# PT08ttl3.net
KiCad netlist of a schematic drawn in EAGLE
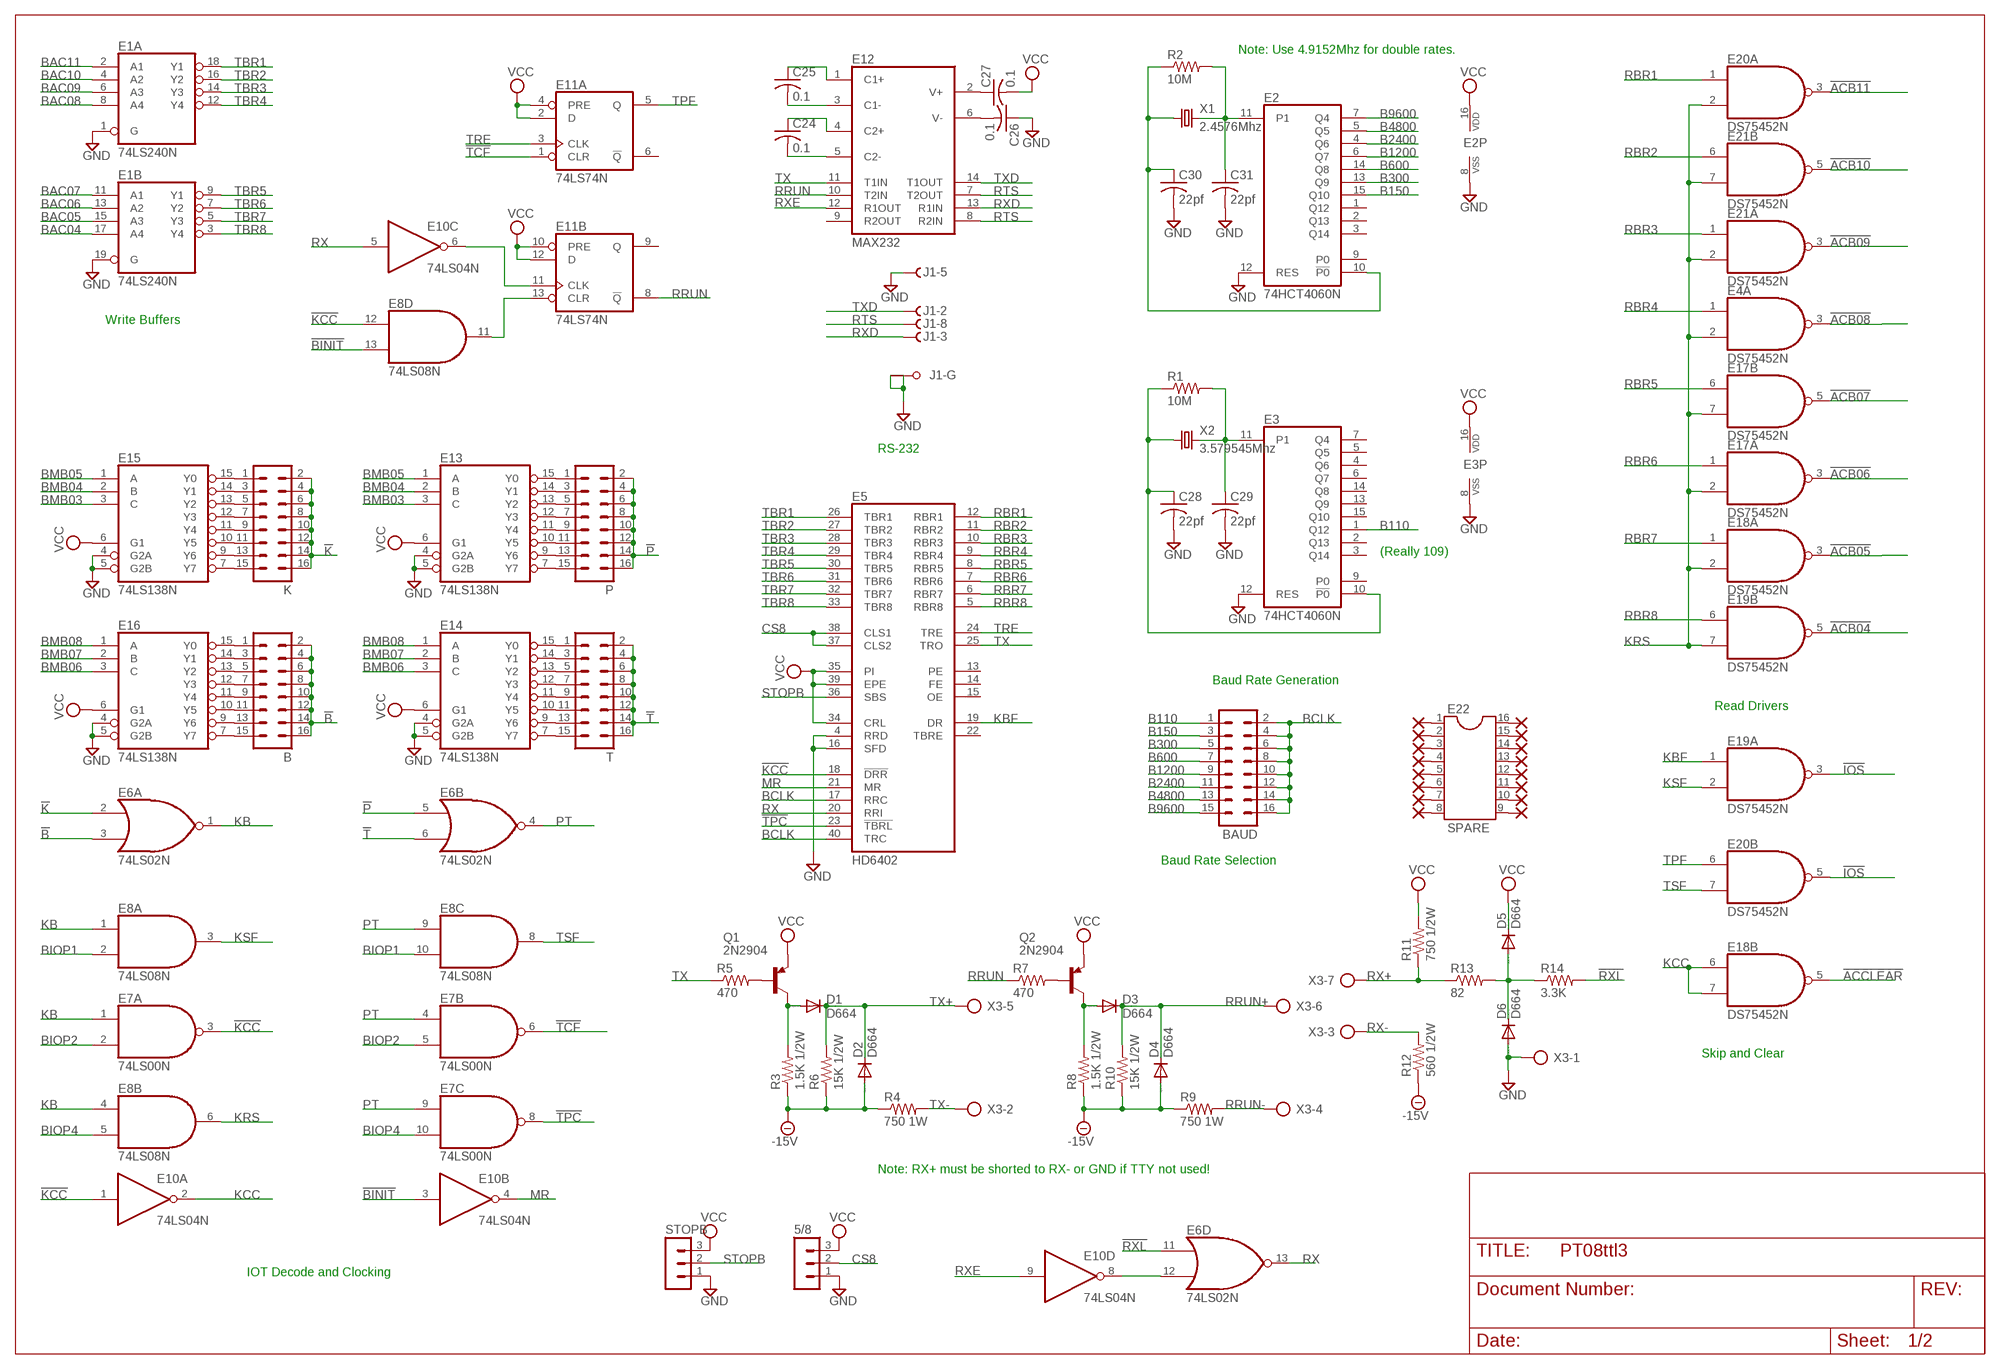
[diagram p0: schematic, sheet 1]
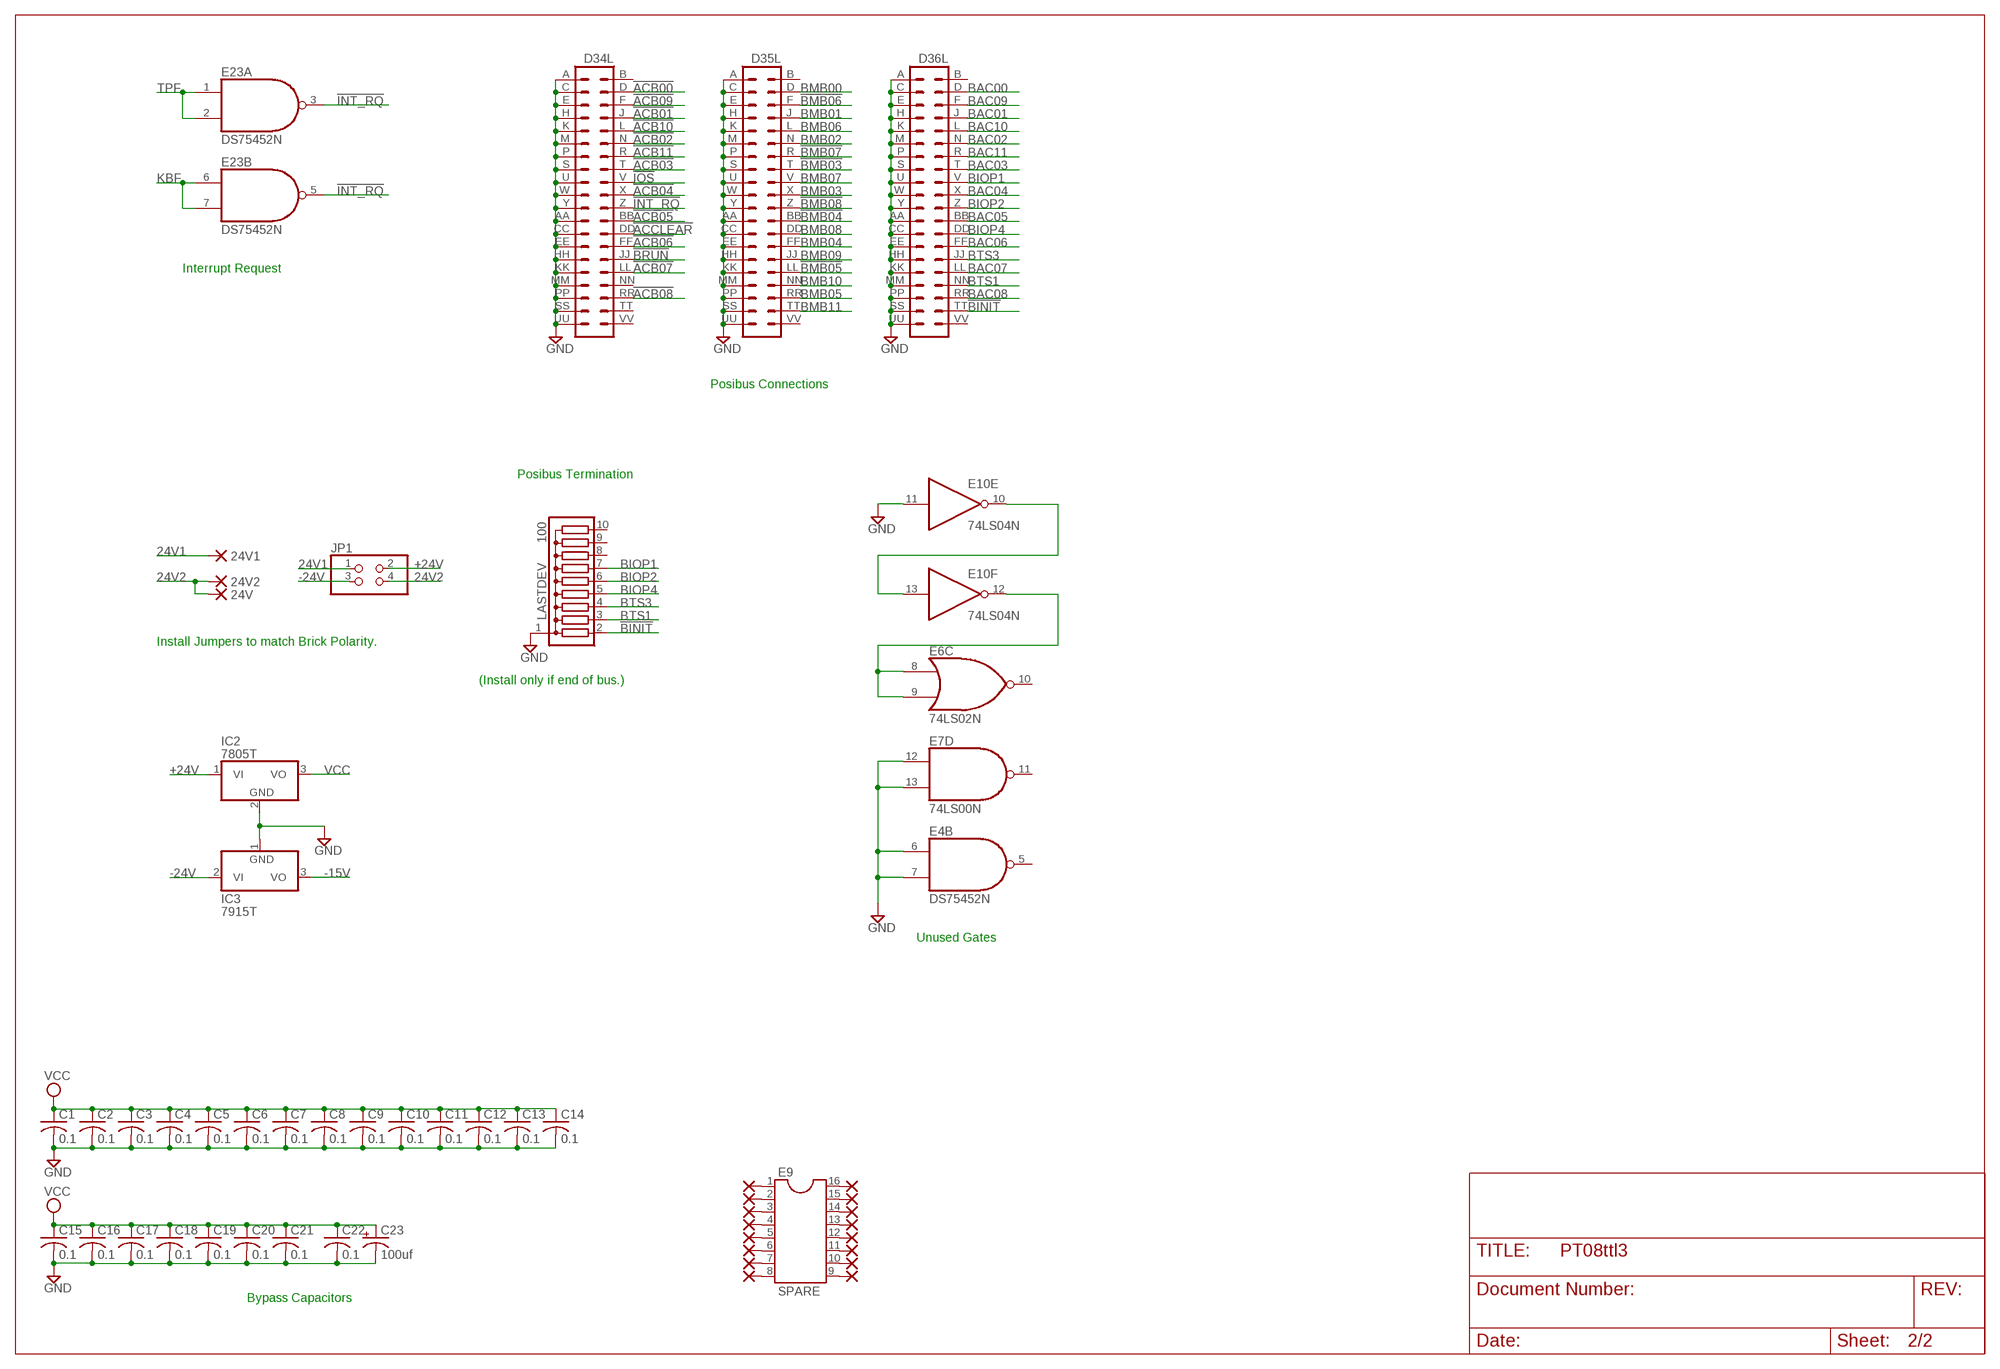
[diagram p1: schematic, sheet 2]

(export (version "E")
  (design (tool "Eeschema 10.0.6"))
  (components
    (comp (ref "5/8")
      (value "MA03-1")
      (footprint "eagle-import:MA03-1")
      (libsource (lib "eagle-import") (part "MA03-1"))
    )
    (comp (ref "B")
      (value "MA08-2")
      (footprint "eagle-import:MA08-2")
      (libsource (lib "eagle-import") (part "MA08-2"))
    )
    (comp (ref "BAUD")
      (value "MA08-2")
      (footprint "eagle-import:MA08-2")
      (libsource (lib "eagle-import") (part "MA08-2"))
    )
    (comp (ref "C24")
      (value "0.1")
      (footprint "eagle-import:C050-025X075")
      (libsource (lib "eagle-import") (part "C-US050-025X075"))
    )
    (comp (ref "C25")
      (value "0.1")
      (footprint "eagle-import:C050-025X075")
      (libsource (lib "eagle-import") (part "C-US050-025X075"))
    )
    (comp (ref "C26")
      (value "0.1")
      (footprint "eagle-import:C050-025X075")
      (libsource (lib "eagle-import") (part "C-US050-025X075"))
    )
    (comp (ref "C27")
      (value "0.1")
      (footprint "eagle-import:C050-025X075")
      (libsource (lib "eagle-import") (part "C-US050-025X075"))
    )
    (comp (ref "C28")
      (value "22pf")
      (footprint "eagle-import:C050-025X075")
      (libsource (lib "eagle-import") (part "C-US050-025X075"))
    )
    (comp (ref "C29")
      (value "22pf")
      (footprint "eagle-import:C050-025X075")
      (libsource (lib "eagle-import") (part "C-US050-025X075"))
    )
    (comp (ref "C30")
      (value "22pf")
      (footprint "eagle-import:C050-025X075")
      (libsource (lib "eagle-import") (part "C-US050-025X075"))
    )
    (comp (ref "C31")
      (value "22pf")
      (footprint "eagle-import:C050-025X075")
      (libsource (lib "eagle-import") (part "C-US050-025X075"))
    )
    (comp (ref "D1")
      (value "D664")
      (footprint "eagle-import:DO35-10")
      (libsource (lib "eagle-import") (part "1N4148DO35-10"))
    )
    (comp (ref "D2")
      (value "D664")
      (footprint "eagle-import:DO35-10")
      (libsource (lib "eagle-import") (part "1N4148DO35-10"))
    )
    (comp (ref "D3")
      (value "D664")
      (footprint "eagle-import:DO35-10")
      (libsource (lib "eagle-import") (part "1N4148DO35-10"))
    )
    (comp (ref "D4")
      (value "D664")
      (footprint "eagle-import:DO35-10")
      (libsource (lib "eagle-import") (part "1N4148DO35-10"))
    )
    (comp (ref "D5")
      (value "D664")
      (footprint "eagle-import:DO35-10")
      (libsource (lib "eagle-import") (part "1N4148DO35-10"))
    )
    (comp (ref "D6")
      (value "D664")
      (footprint "eagle-import:DO35-10")
      (libsource (lib "eagle-import") (part "1N4148DO35-10"))
    )
    (comp (ref "E1")
      (value "74LS240N")
      (footprint "eagle-import:DIL20")
      (libsource (lib "eagle-import") (part "74240NLS"))
    )
    (comp (ref "E2")
      (value "74HCT4060N")
      (footprint "eagle-import:DIL16")
      (libsource (lib "eagle-import") (part "4060N"))
    )
    (comp (ref "E3")
      (value "74HCT4060N")
      (footprint "eagle-import:DIL16")
      (libsource (lib "eagle-import") (part "4060N"))
    )
    (comp (ref "E4")
      (value "DS75452N")
      (footprint "eagle-import:DIL08")
      (libsource (lib "eagle-import") (part "DS75452N"))
    )
    (comp (ref "E5")
      (value "HD6402")
      (footprint "eagle-import:DIL40")
      (libsource (lib "eagle-import") (part "HD6402"))
    )
    (comp (ref "E6")
      (value "74LS02N")
      (footprint "eagle-import:DIL14")
      (libsource (lib "eagle-import") (part "7402NLS"))
    )
    (comp (ref "E7")
      (value "74LS00N")
      (footprint "eagle-import:DIL14")
      (libsource (lib "eagle-import") (part "7400NLS"))
    )
    (comp (ref "E8")
      (value "74LS08N")
      (footprint "eagle-import:DIL14")
      (libsource (lib "eagle-import") (part "7408NLS"))
    )
    (comp (ref "E10")
      (value "74LS04N")
      (footprint "eagle-import:DIL14")
      (libsource (lib "eagle-import") (part "7404NLS"))
    )
    (comp (ref "E11")
      (value "74LS74N")
      (footprint "eagle-import:DIL14")
      (libsource (lib "eagle-import") (part "7474NLS"))
    )
    (comp (ref "E12")
      (value "MAX232")
      (footprint "eagle-import:DIL16")
      (fields (field (name "MF") "MAXIM") (field (name "MPN") "MAX232ACPE+"))
      (libsource (lib "eagle-import") (part "MAX232"))
    )
    (comp (ref "E13")
      (value "74LS138N")
      (footprint "eagle-import:DIL16")
      (libsource (lib "eagle-import") (part "74138NLS"))
    )
    (comp (ref "E14")
      (value "74LS138N")
      (footprint "eagle-import:DIL16")
      (libsource (lib "eagle-import") (part "74138NLS"))
    )
    (comp (ref "E15")
      (value "74LS138N")
      (footprint "eagle-import:DIL16")
      (libsource (lib "eagle-import") (part "74138NLS"))
    )
    (comp (ref "E16")
      (value "74LS138N")
      (footprint "eagle-import:DIL16")
      (libsource (lib "eagle-import") (part "74138NLS"))
    )
    (comp (ref "E17")
      (value "DS75452N")
      (footprint "eagle-import:DIL08")
      (libsource (lib "eagle-import") (part "DS75452N"))
    )
    (comp (ref "E18")
      (value "DS75452N")
      (footprint "eagle-import:DIL08")
      (libsource (lib "eagle-import") (part "DS75452N"))
    )
    (comp (ref "E19")
      (value "DS75452N")
      (footprint "eagle-import:DIL08")
      (libsource (lib "eagle-import") (part "DS75452N"))
    )
    (comp (ref "E20")
      (value "DS75452N")
      (footprint "eagle-import:DIL08")
      (libsource (lib "eagle-import") (part "DS75452N"))
    )
    (comp (ref "E21")
      (value "DS75452N")
      (footprint "eagle-import:DIL08")
      (libsource (lib "eagle-import") (part "DS75452N"))
    )
    (comp (ref "E22")
      (value "SPARE")
      (footprint "eagle-import:DIL16")
      (libsource (lib "eagle-import") (part "DIL16"))
    )
    (comp (ref "J1")
      (value "F09HPS")
      (footprint "eagle-import:F09HP")
      (libsource (lib "eagle-import") (part "F09HPS"))
    )
    (comp (ref "K")
      (value "MA08-2")
      (footprint "eagle-import:MA08-2")
      (libsource (lib "eagle-import") (part "MA08-2"))
    )
    (comp (ref "P")
      (value "MA08-2")
      (footprint "eagle-import:MA08-2")
      (libsource (lib "eagle-import") (part "MA08-2"))
    )
    (comp (ref "PAD18")
      (value "1,6/0,8")
      (footprint "eagle-import:1,6_0,8")
      (libsource (lib "eagle-import") (part "1,6/0,8"))
    )
    (comp (ref "PAD19")
      (value "1,6/0,8")
      (footprint "eagle-import:1,6_0,8")
      (libsource (lib "eagle-import") (part "1,6/0,8"))
    )
    (comp (ref "PAD28")
      (value "1,6/0,8")
      (footprint "eagle-import:1,6_0,8")
      (libsource (lib "eagle-import") (part "1,6/0,8"))
    )
    (comp (ref "PAD29")
      (value "1,6/0,8")
      (footprint "eagle-import:1,6_0,8")
      (libsource (lib "eagle-import") (part "1,6/0,8"))
    )
    (comp (ref "PAD30")
      (value "1,6/0,8")
      (footprint "eagle-import:1,6_0,8")
      (libsource (lib "eagle-import") (part "1,6/0,8"))
    )
    (comp (ref "PAD31")
      (value "1,6/0,8")
      (footprint "eagle-import:1,6_0,8")
      (libsource (lib "eagle-import") (part "1,6/0,8"))
    )
    (comp (ref "PAD32")
      (value "1,6/0,8")
      (footprint "eagle-import:1,6_0,8")
      (libsource (lib "eagle-import") (part "1,6/0,8"))
    )
    (comp (ref "PAD33")
      (value "1,6/0,8")
      (footprint "eagle-import:1,6_0,8")
      (libsource (lib "eagle-import") (part "1,6/0,8"))
    )
    (comp (ref "PAD34")
      (value "1,6/0,8")
      (footprint "eagle-import:1,6_0,8")
      (libsource (lib "eagle-import") (part "1,6/0,8"))
    )
    (comp (ref "PAD35")
      (value "1,6/0,8")
      (footprint "eagle-import:1,6_0,8")
      (libsource (lib "eagle-import") (part "1,6/0,8"))
    )
    (comp (ref "PAD36")
      (value "1,6/0,8")
      (footprint "eagle-import:1,6_0,8")
      (libsource (lib "eagle-import") (part "1,6/0,8"))
    )
    (comp (ref "PAD37")
      (value "1,6/0,8")
      (footprint "eagle-import:1,6_0,8")
      (libsource (lib "eagle-import") (part "1,6/0,8"))
    )
    (comp (ref "PAD38")
      (value "1,6/0,8")
      (footprint "eagle-import:1,6_0,8")
      (libsource (lib "eagle-import") (part "1,6/0,8"))
    )
    (comp (ref "PAD39")
      (value "1,6/0,8")
      (footprint "eagle-import:1,6_0,8")
      (libsource (lib "eagle-import") (part "1,6/0,8"))
    )
    (comp (ref "PAD40")
      (value "1,6/0,8")
      (footprint "eagle-import:1,6_0,8")
      (libsource (lib "eagle-import") (part "1,6/0,8"))
    )
    (comp (ref "PAD41")
      (value "1,6/0,8")
      (footprint "eagle-import:1,6_0,8")
      (libsource (lib "eagle-import") (part "1,6/0,8"))
    )
    (comp (ref "Q1")
      (value "2N2904")
      (footprint "eagle-import:TO39")
      (libsource (lib "eagle-import") (part "2N2904"))
    )
    (comp (ref "Q2")
      (value "2N2904")
      (footprint "eagle-import:TO39")
      (libsource (lib "eagle-import") (part "2N2904"))
    )
    (comp (ref "R1")
      (value "10M")
      (footprint "eagle-import:0207_10")
      (libsource (lib "eagle-import") (part "R-US_0207/10"))
    )
    (comp (ref "R2")
      (value "10M")
      (footprint "eagle-import:0207_10")
      (libsource (lib "eagle-import") (part "R-US_0207/10"))
    )
    (comp (ref "R3")
      (value "1.5K 1/2W")
      (footprint "eagle-import:0207_10")
      (libsource (lib "eagle-import") (part "R-US_0207/10"))
    )
    (comp (ref "R4")
      (value "750 1W")
      (footprint "eagle-import:0207_10")
      (libsource (lib "eagle-import") (part "R-US_0207/10"))
    )
    (comp (ref "R5")
      (value "470")
      (footprint "eagle-import:0207_10")
      (libsource (lib "eagle-import") (part "R-US_0207/10"))
    )
    (comp (ref "R6")
      (value "15K 1/2W")
      (footprint "eagle-import:0207_10")
      (libsource (lib "eagle-import") (part "R-US_0207/10"))
    )
    (comp (ref "R7")
      (value "470")
      (footprint "eagle-import:0207_10")
      (libsource (lib "eagle-import") (part "R-US_0207/10"))
    )
    (comp (ref "R8")
      (value "1.5K 1/2W")
      (footprint "eagle-import:0207_10")
      (libsource (lib "eagle-import") (part "R-US_0207/10"))
    )
    (comp (ref "R9")
      (value "750 1W")
      (footprint "eagle-import:0207_10")
      (libsource (lib "eagle-import") (part "R-US_0207/10"))
    )
    (comp (ref "R10")
      (value "15K 1/2W")
      (footprint "eagle-import:0207_10")
      (libsource (lib "eagle-import") (part "R-US_0207/10"))
    )
    (comp (ref "R11")
      (value "750 1/2W")
      (footprint "eagle-import:0207_10")
      (libsource (lib "eagle-import") (part "R-US_0207/10"))
    )
    (comp (ref "R12")
      (value "560 1/2W")
      (footprint "eagle-import:0207_10")
      (libsource (lib "eagle-import") (part "R-US_0207/10"))
    )
    (comp (ref "R13")
      (value "82")
      (footprint "eagle-import:0207_10")
      (libsource (lib "eagle-import") (part "R-US_0207/10"))
    )
    (comp (ref "R14")
      (value "3.3K")
      (footprint "eagle-import:0207_10")
      (libsource (lib "eagle-import") (part "R-US_0207/10"))
    )
    (comp (ref "STOPB")
      (value "MA03-1")
      (footprint "eagle-import:MA03-1")
      (libsource (lib "eagle-import") (part "MA03-1"))
    )
    (comp (ref "T")
      (value "MA08-2")
      (footprint "eagle-import:MA08-2")
      (libsource (lib "eagle-import") (part "MA08-2"))
    )
    (comp (ref "X1")
      (value "2.4576Mhz")
      (footprint "eagle-import:HC49U-V")
      (libsource (lib "eagle-import") (part "CRYSTALHC49U-V"))
    )
    (comp (ref "X2")
      (value "3.579545Mhz")
      (footprint "eagle-import:HC49U-V")
      (libsource (lib "eagle-import") (part "CRYSTALHC49U-V"))
    )
    (comp (ref "X3")
      (value "AK300/7")
      (footprint "eagle-import:AK300_7")
      (libsource (lib "eagle-import") (part "AK300/7"))
    )
    (comp (ref "24V")
      (value "PAD-0820")
      (footprint "eagle-import:0820")
      (libsource (lib "eagle-import") (part "PAD-0820"))
    )
    (comp (ref "24V1")
      (value "PAD-0820")
      (footprint "eagle-import:0820")
      (libsource (lib "eagle-import") (part "PAD-0820"))
    )
    (comp (ref "24V2")
      (value "PAD-0820")
      (footprint "eagle-import:0820")
      (libsource (lib "eagle-import") (part "PAD-0820"))
    )
    (comp (ref "C1")
      (value "0.1")
      (footprint "eagle-import:C050-025X075")
      (libsource (lib "eagle-import") (part "C-US050-025X075"))
    )
    (comp (ref "C2")
      (value "0.1")
      (footprint "eagle-import:C050-025X075")
      (libsource (lib "eagle-import") (part "C-US050-025X075"))
    )
    (comp (ref "C3")
      (value "0.1")
      (footprint "eagle-import:C050-025X075")
      (libsource (lib "eagle-import") (part "C-US050-025X075"))
    )
    (comp (ref "C4")
      (value "0.1")
      (footprint "eagle-import:C050-025X075")
      (libsource (lib "eagle-import") (part "C-US050-025X075"))
    )
    (comp (ref "C5")
      (value "0.1")
      (footprint "eagle-import:C050-025X075")
      (libsource (lib "eagle-import") (part "C-US050-025X075"))
    )
    (comp (ref "C6")
      (value "0.1")
      (footprint "eagle-import:C050-025X075")
      (libsource (lib "eagle-import") (part "C-US050-025X075"))
    )
    (comp (ref "C7")
      (value "0.1")
      (footprint "eagle-import:C050-025X075")
      (libsource (lib "eagle-import") (part "C-US050-025X075"))
    )
    (comp (ref "C8")
      (value "0.1")
      (footprint "eagle-import:C050-025X075")
      (libsource (lib "eagle-import") (part "C-US050-025X075"))
    )
    (comp (ref "C9")
      (value "0.1")
      (footprint "eagle-import:C050-025X075")
      (libsource (lib "eagle-import") (part "C-US050-025X075"))
    )
    (comp (ref "C10")
      (value "0.1")
      (footprint "eagle-import:C050-025X075")
      (libsource (lib "eagle-import") (part "C-US050-025X075"))
    )
    (comp (ref "C11")
      (value "0.1")
      (footprint "eagle-import:C050-025X075")
      (libsource (lib "eagle-import") (part "C-US050-025X075"))
    )
    (comp (ref "C12")
      (value "0.1")
      (footprint "eagle-import:C050-025X075")
      (libsource (lib "eagle-import") (part "C-US050-025X075"))
    )
    (comp (ref "C13")
      (value "0.1")
      (footprint "eagle-import:C050-025X075")
      (libsource (lib "eagle-import") (part "C-US050-025X075"))
    )
    (comp (ref "C14")
      (value "0.1")
      (footprint "eagle-import:C050-025X075")
      (libsource (lib "eagle-import") (part "C-US050-025X075"))
    )
    (comp (ref "C15")
      (value "0.1")
      (footprint "eagle-import:C050-025X075")
      (libsource (lib "eagle-import") (part "C-US050-025X075"))
    )
    (comp (ref "C16")
      (value "0.1")
      (footprint "eagle-import:C050-025X075")
      (libsource (lib "eagle-import") (part "C-US050-025X075"))
    )
    (comp (ref "C17")
      (value "0.1")
      (footprint "eagle-import:C050-025X075")
      (libsource (lib "eagle-import") (part "C-US050-025X075"))
    )
    (comp (ref "C18")
      (value "0.1")
      (footprint "eagle-import:C050-025X075")
      (libsource (lib "eagle-import") (part "C-US050-025X075"))
    )
    (comp (ref "C19")
      (value "0.1")
      (footprint "eagle-import:C050-025X075")
      (libsource (lib "eagle-import") (part "C-US050-025X075"))
    )
    (comp (ref "C20")
      (value "0.1")
      (footprint "eagle-import:C050-025X075")
      (libsource (lib "eagle-import") (part "C-US050-025X075"))
    )
    (comp (ref "C21")
      (value "0.1")
      (footprint "eagle-import:C050-025X075")
      (libsource (lib "eagle-import") (part "C-US050-025X075"))
    )
    (comp (ref "C22")
      (value "0.1")
      (footprint "eagle-import:C050-025X075")
      (libsource (lib "eagle-import") (part "C-US050-025X075"))
    )
    (comp (ref "C23")
      (value "100uf")
      (footprint "eagle-import:E22-9")
      (libsource (lib "eagle-import") (part "CPOL-USE22-9AXIAL"))
    )
    (comp (ref "D34L")
      (value "DEC40PINH")
      (footprint "eagle-import:DEC40PINH")
      (libsource (lib "eagle-import") (part "DEC40PINH"))
    )
    (comp (ref "D35L")
      (value "DEC40PINH")
      (footprint "eagle-import:DEC40PINH")
      (libsource (lib "eagle-import") (part "DEC40PINH"))
    )
    (comp (ref "D36L")
      (value "DEC40PINH")
      (footprint "eagle-import:DEC40PINH")
      (libsource (lib "eagle-import") (part "DEC40PINH"))
    )
    (comp (ref "E9")
      (value "SPARE")
      (footprint "eagle-import:DIL16")
      (libsource (lib "eagle-import") (part "DIL16"))
    )
    (comp (ref "E23")
      (value "DS75452N")
      (footprint "eagle-import:DIL08")
      (libsource (lib "eagle-import") (part "DS75452N"))
    )
    (comp (ref "IC2")
      (value "7805T")
      (footprint "eagle-import:TO220H")
      (libsource (lib "eagle-import") (part "78T05"))
    )
    (comp (ref "IC3")
      (value "7915T")
      (footprint "eagle-import:TO220H")
      (libsource (lib "eagle-import") (part "79T15"))
    )
    (comp (ref "JP1")
      (value "PINHD-2X2")
      (footprint "eagle-import:2X02")
      (libsource (lib "eagle-import") (part "PINHD-2X2"))
    )
    (comp (ref "LASTDEV")
      (value "100")
      (footprint "eagle-import:SIL10")
      (libsource (lib "eagle-import") (part "G09R"))
    )
    (comp (ref "PAD1")
      (value "1,6/0,8")
      (footprint "eagle-import:1,6_0,8")
      (libsource (lib "eagle-import") (part "1,6/0,8"))
    )
    (comp (ref "PAD2")
      (value "1,6/0,8")
      (footprint "eagle-import:1,6_0,8")
      (libsource (lib "eagle-import") (part "1,6/0,8"))
    )
    (comp (ref "PAD3")
      (value "1,6/0,8")
      (footprint "eagle-import:1,6_0,8")
      (libsource (lib "eagle-import") (part "1,6/0,8"))
    )
    (comp (ref "PAD4")
      (value "1,6/0,8")
      (footprint "eagle-import:1,6_0,8")
      (libsource (lib "eagle-import") (part "1,6/0,8"))
    )
    (comp (ref "PAD5")
      (value "1,6/0,8")
      (footprint "eagle-import:1,6_0,8")
      (libsource (lib "eagle-import") (part "1,6/0,8"))
    )
    (comp (ref "PAD6")
      (value "1,6/0,8")
      (footprint "eagle-import:1,6_0,8")
      (libsource (lib "eagle-import") (part "1,6/0,8"))
    )
    (comp (ref "PAD7")
      (value "1,6/0,8")
      (footprint "eagle-import:1,6_0,8")
      (libsource (lib "eagle-import") (part "1,6/0,8"))
    )
    (comp (ref "PAD8")
      (value "1,6/0,8")
      (footprint "eagle-import:1,6_0,8")
      (libsource (lib "eagle-import") (part "1,6/0,8"))
    )
    (comp (ref "PAD9")
      (value "1,6/0,8")
      (footprint "eagle-import:1,6_0,8")
      (libsource (lib "eagle-import") (part "1,6/0,8"))
    )
    (comp (ref "PAD42")
      (value "1,6/0,8")
      (footprint "eagle-import:1,6_0,8")
      (libsource (lib "eagle-import") (part "1,6/0,8"))
    )
    (comp (ref "PAD43")
      (value "1,6/0,8")
      (footprint "eagle-import:1,6_0,8")
      (libsource (lib "eagle-import") (part "1,6/0,8"))
    )
    (comp (ref "PAD44")
      (value "1,6/0,8")
      (footprint "eagle-import:1,6_0,8")
      (libsource (lib "eagle-import") (part "1,6/0,8"))
    )
    (comp (ref "PAD45")
      (value "1,6/0,8")
      (footprint "eagle-import:1,6_0,8")
      (libsource (lib "eagle-import") (part "1,6/0,8"))
    )
    (comp (ref "PAD46")
      (value "1,6/0,8")
      (footprint "eagle-import:1,6_0,8")
      (libsource (lib "eagle-import") (part "1,6/0,8"))
    )
    (comp (ref "PAD47")
      (value "1,6/0,8")
      (footprint "eagle-import:1,6_0,8")
      (libsource (lib "eagle-import") (part "1,6/0,8"))
    )
    (comp (ref "PAD48")
      (value "1,6/0,8")
      (footprint "eagle-import:1,6_0,8")
      (libsource (lib "eagle-import") (part "1,6/0,8"))
    )
  )
  (nets
    (net (code "1") (name "+24V") (class "Default")
      (node (ref "IC2") (pin "1") (pinfunction "VI_1") (pintype "input"))
      (node (ref "JP1") (pin "2") (pinfunction "2_2") (pintype "passive"))
    )
    (net (code "2") (name "-15V") (class "Default")
      (node (ref "D2") (pin "A") (pinfunction "A_A") (pintype "passive"))
      (node (ref "D4") (pin "A") (pinfunction "A_A") (pintype "passive"))
      (node (ref "IC3") (pin "3") (pinfunction "VO_3") (pintype "passive"))
      (node (ref "R10") (pin "1") (pinfunction "1_1") (pintype "passive"))
      (node (ref "R12") (pin "1") (pinfunction "1_1") (pintype "passive"))
      (node (ref "R3") (pin "1") (pinfunction "1_1") (pintype "passive"))
      (node (ref "R4") (pin "1") (pinfunction "1_1") (pintype "passive"))
      (node (ref "R6") (pin "1") (pinfunction "1_1") (pintype "passive"))
      (node (ref "R8") (pin "1") (pinfunction "1_1") (pintype "passive"))
      (node (ref "R9") (pin "1") (pinfunction "1_1") (pintype "passive"))
    )
    (net (code "3") (name "-24V") (class "Default")
      (node (ref "IC3") (pin "2") (pinfunction "VI_2") (pintype "input"))
      (node (ref "JP1") (pin "3") (pinfunction "3_3") (pintype "passive"))
    )
    (net (code "4") (name "24V1") (class "Default")
      (node (ref "24V1") (pin "P$1") (pinfunction "P_P$1") (pintype "passive"))
      (node (ref "JP1") (pin "1") (pinfunction "1_1") (pintype "passive"))
    )
    (net (code "5") (name "24V2") (class "Default")
      (node (ref "24V") (pin "P$1") (pinfunction "P_P$1") (pintype "passive"))
      (node (ref "24V2") (pin "P$1") (pinfunction "P_P$1") (pintype "passive"))
      (node (ref "JP1") (pin "4") (pinfunction "4_4") (pintype "passive"))
    )
    (net (code "6") (name "B110") (class "Default")
      (node (ref "BAUD") (pin "1") (pinfunction "1_1") (pintype "passive"))
      (node (ref "E3") (pin "1") (pinfunction "Q12_1") (pintype "output"))
    )
    (net (code "7") (name "B150") (class "Default")
      (node (ref "BAUD") (pin "3") (pinfunction "3_3") (pintype "passive"))
      (node (ref "E2") (pin "15") (pinfunction "Q10_15") (pintype "output"))
    )
    (net (code "8") (name "B300") (class "Default")
      (node (ref "BAUD") (pin "5") (pinfunction "5_5") (pintype "passive"))
      (node (ref "E2") (pin "13") (pinfunction "Q9_13") (pintype "output"))
    )
    (net (code "9") (name "B600") (class "Default")
      (node (ref "BAUD") (pin "7") (pinfunction "7_7") (pintype "passive"))
      (node (ref "E2") (pin "14") (pinfunction "Q8_14") (pintype "output"))
    )
    (net (code "10") (name "B1200") (class "Default")
      (node (ref "BAUD") (pin "9") (pinfunction "9_9") (pintype "passive"))
      (node (ref "E2") (pin "6") (pinfunction "Q7_6") (pintype "output"))
    )
    (net (code "11") (name "B2400") (class "Default")
      (node (ref "BAUD") (pin "11") (pinfunction "11_11") (pintype "passive"))
      (node (ref "E2") (pin "4") (pinfunction "Q6_4") (pintype "output"))
    )
    (net (code "12") (name "B4800") (class "Default")
      (node (ref "BAUD") (pin "13") (pinfunction "13_13") (pintype "passive"))
      (node (ref "E2") (pin "5") (pinfunction "Q5_5") (pintype "output"))
    )
    (net (code "13") (name "B9600") (class "Default")
      (node (ref "BAUD") (pin "15") (pinfunction "15_15") (pintype "passive"))
      (node (ref "E2") (pin "7") (pinfunction "Q4_7") (pintype "output"))
    )
    (net (code "14") (name "BAC00") (class "Default")
      (node (ref "D36L") (pin "D") (pinfunction "4_D") (pintype "bidirectional"))
    )
    (net (code "15") (name "BAC01") (class "Default")
      (node (ref "D36L") (pin "J") (pinfunction "8_J") (pintype "bidirectional"))
    )
    (net (code "16") (name "BAC02") (class "Default")
      (node (ref "D36L") (pin "N") (pinfunction "12_N") (pintype "bidirectional"))
    )
    (net (code "17") (name "BAC03") (class "Default")
      (node (ref "D36L") (pin "T") (pinfunction "16_T") (pintype "bidirectional"))
    )
    (net (code "18") (name "BAC04") (class "Default")
      (node (ref "D36L") (pin "X") (pinfunction "20_X") (pintype "bidirectional"))
      (node (ref "E1") (pin "17") (pinfunction "A4_17") (pintype "input"))
    )
    (net (code "19") (name "BAC05") (class "Default")
      (node (ref "D36L") (pin "BB") (pinfunction "24_BB") (pintype "bidirectional"))
      (node (ref "E1") (pin "15") (pinfunction "A3_15") (pintype "input"))
    )
    (net (code "20") (name "BAC06") (class "Default")
      (node (ref "D36L") (pin "FF") (pinfunction "28_FF") (pintype "bidirectional"))
      (node (ref "E1") (pin "13") (pinfunction "A2_13") (pintype "input"))
    )
    (net (code "21") (name "BAC07") (class "Default")
      (node (ref "D36L") (pin "LL") (pinfunction "32_LL") (pintype "bidirectional"))
      (node (ref "E1") (pin "11") (pinfunction "A1_11") (pintype "input"))
    )
    (net (code "22") (name "BAC08") (class "Default")
      (node (ref "D36L") (pin "RR") (pinfunction "36_RR") (pintype "bidirectional"))
      (node (ref "E1") (pin "8") (pinfunction "A4_8") (pintype "input"))
    )
    (net (code "23") (name "BAC09") (class "Default")
      (node (ref "D36L") (pin "F") (pinfunction "6_F") (pintype "bidirectional"))
      (node (ref "E1") (pin "6") (pinfunction "A3_6") (pintype "input"))
    )
    (net (code "24") (name "BAC10") (class "Default")
      (node (ref "D36L") (pin "L") (pinfunction "10_L") (pintype "bidirectional"))
      (node (ref "E1") (pin "4") (pinfunction "A2_4") (pintype "input"))
    )
    (net (code "25") (name "BAC11") (class "Default")
      (node (ref "D36L") (pin "R") (pinfunction "14_R") (pintype "bidirectional"))
      (node (ref "E1") (pin "2") (pinfunction "A1_2") (pintype "input"))
    )
    (net (code "26") (name "BCLK") (class "Default")
      (node (ref "BAUD") (pin "10") (pinfunction "10_10") (pintype "passive"))
      (node (ref "BAUD") (pin "12") (pinfunction "12_12") (pintype "passive"))
      (node (ref "BAUD") (pin "14") (pinfunction "14_14") (pintype "passive"))
      (node (ref "BAUD") (pin "16") (pinfunction "16_16") (pintype "passive"))
      (node (ref "BAUD") (pin "2") (pinfunction "2_2") (pintype "passive"))
      (node (ref "BAUD") (pin "4") (pinfunction "4_4") (pintype "passive"))
      (node (ref "BAUD") (pin "6") (pinfunction "6_6") (pintype "passive"))
      (node (ref "BAUD") (pin "8") (pinfunction "8_8") (pintype "passive"))
      (node (ref "E5") (pin "17") (pinfunction "RRC_17") (pintype "input"))
      (node (ref "E5") (pin "40") (pinfunction "TRC_40") (pintype "input"))
    )
    (net (code "27") (name "BIOP1") (class "Default")
      (node (ref "D36L") (pin "V") (pinfunction "18_V") (pintype "bidirectional"))
      (node (ref "E8") (pin "10") (pinfunction "I1_10") (pintype "input"))
      (node (ref "E8") (pin "2") (pinfunction "I1_2") (pintype "input"))
      (node (ref "LASTDEV") (pin "7") (pinfunction "7_7") (pintype "passive"))
    )
    (net (code "28") (name "BIOP2") (class "Default")
      (node (ref "D36L") (pin "Z") (pinfunction "22_Z") (pintype "bidirectional"))
      (node (ref "E7") (pin "2") (pinfunction "I1_2") (pintype "input"))
      (node (ref "E7") (pin "5") (pinfunction "I1_5") (pintype "input"))
      (node (ref "LASTDEV") (pin "6") (pinfunction "6_6") (pintype "passive"))
    )
    (net (code "29") (name "BIOP4") (class "Default")
      (node (ref "D36L") (pin "DD") (pinfunction "26_DD") (pintype "bidirectional"))
      (node (ref "E7") (pin "10") (pinfunction "I1_10") (pintype "input"))
      (node (ref "E8") (pin "5") (pinfunction "I1_5") (pintype "input"))
      (node (ref "LASTDEV") (pin "5") (pinfunction "5_5") (pintype "passive"))
    )
    (net (code "30") (name "BMB00") (class "Default")
      (node (ref "D35L") (pin "D") (pinfunction "4_D") (pintype "bidirectional"))
    )
    (net (code "31") (name "BMB01") (class "Default")
      (node (ref "D35L") (pin "J") (pinfunction "8_J") (pintype "bidirectional"))
    )
    (net (code "32") (name "BMB02") (class "Default")
      (node (ref "D35L") (pin "N") (pinfunction "12_N") (pintype "bidirectional"))
    )
    (net (code "33") (name "BMB03") (class "Default")
      (node (ref "D35L") (pin "X") (pinfunction "20_X") (pintype "bidirectional"))
      (node (ref "E13") (pin "3") (pinfunction "C_3") (pintype "input"))
      (node (ref "E15") (pin "3") (pinfunction "C_3") (pintype "input"))
    )
    (net (code "34") (name "BMB04") (class "Default")
      (node (ref "D35L") (pin "FF") (pinfunction "28_FF") (pintype "bidirectional"))
      (node (ref "E13") (pin "2") (pinfunction "B_2") (pintype "input"))
      (node (ref "E15") (pin "2") (pinfunction "B_2") (pintype "input"))
    )
    (net (code "35") (name "BMB05") (class "Default")
      (node (ref "D35L") (pin "RR") (pinfunction "36_RR") (pintype "bidirectional"))
      (node (ref "E13") (pin "1") (pinfunction "A_1") (pintype "input"))
      (node (ref "E15") (pin "1") (pinfunction "A_1") (pintype "input"))
    )
    (net (code "36") (name "BMB06") (class "Default")
      (node (ref "D35L") (pin "L") (pinfunction "10_L") (pintype "bidirectional"))
      (node (ref "E14") (pin "3") (pinfunction "C_3") (pintype "input"))
      (node (ref "E16") (pin "3") (pinfunction "C_3") (pintype "input"))
    )
    (net (code "37") (name "BMB07") (class "Default")
      (node (ref "D35L") (pin "V") (pinfunction "18_V") (pintype "bidirectional"))
      (node (ref "E14") (pin "2") (pinfunction "B_2") (pintype "input"))
      (node (ref "E16") (pin "2") (pinfunction "B_2") (pintype "input"))
    )
    (net (code "38") (name "BMB08") (class "Default")
      (node (ref "D35L") (pin "DD") (pinfunction "26_DD") (pintype "bidirectional"))
      (node (ref "E14") (pin "1") (pinfunction "A_1") (pintype "input"))
      (node (ref "E16") (pin "1") (pinfunction "A_1") (pintype "input"))
    )
    (net (code "39") (name "BMB09") (class "Default")
      (node (ref "D35L") (pin "JJ") (pinfunction "30_JJ") (pintype "bidirectional"))
    )
    (net (code "40") (name "BMB10") (class "Default")
      (node (ref "D35L") (pin "NN") (pinfunction "34_NN") (pintype "bidirectional"))
    )
    (net (code "41") (name "BMB11") (class "Default")
      (node (ref "D35L") (pin "TT") (pinfunction "38_TT") (pintype "bidirectional"))
    )
    (net (code "42") (name "BTS1") (class "Default")
      (node (ref "D36L") (pin "NN") (pinfunction "34_NN") (pintype "bidirectional"))
      (node (ref "LASTDEV") (pin "3") (pinfunction "3_3") (pintype "passive"))
    )
    (net (code "43") (name "BTS3") (class "Default")
      (node (ref "D36L") (pin "JJ") (pinfunction "30_JJ") (pintype "bidirectional"))
      (node (ref "LASTDEV") (pin "4") (pinfunction "4_4") (pintype "passive"))
    )
    (net (code "44") (name "CS8") (class "Default")
      (node (ref "5/8") (pin "2") (pinfunction "2_2") (pintype "passive"))
      (node (ref "E5") (pin "37") (pinfunction "CLS2_37") (pintype "input"))
      (node (ref "E5") (pin "38") (pinfunction "CLS1_38") (pintype "input"))
    )
    (net (code "45") (name "GND") (class "Default")
      (node (ref "5/8") (pin "1") (pinfunction "1_1") (pintype "passive"))
      (node (ref "C1") (pin "2") (pinfunction "2_2") (pintype "passive"))
      (node (ref "C10") (pin "2") (pinfunction "2_2") (pintype "passive"))
      (node (ref "C11") (pin "2") (pinfunction "2_2") (pintype "passive"))
      (node (ref "C12") (pin "2") (pinfunction "2_2") (pintype "passive"))
      (node (ref "C13") (pin "2") (pinfunction "2_2") (pintype "passive"))
      (node (ref "C14") (pin "2") (pinfunction "2_2") (pintype "passive"))
      (node (ref "C15") (pin "2") (pinfunction "2_2") (pintype "passive"))
      (node (ref "C16") (pin "2") (pinfunction "2_2") (pintype "passive"))
      (node (ref "C17") (pin "2") (pinfunction "2_2") (pintype "passive"))
      (node (ref "C18") (pin "2") (pinfunction "2_2") (pintype "passive"))
      (node (ref "C19") (pin "2") (pinfunction "2_2") (pintype "passive"))
      (node (ref "C2") (pin "2") (pinfunction "2_2") (pintype "passive"))
      (node (ref "C20") (pin "2") (pinfunction "2_2") (pintype "passive"))
      (node (ref "C21") (pin "2") (pinfunction "2_2") (pintype "passive"))
      (node (ref "C22") (pin "2") (pinfunction "2_2") (pintype "passive"))
      (node (ref "C23") (pin "-") (pinfunction "-_-") (pintype "passive"))
      (node (ref "C26") (pin "1") (pinfunction "1_1") (pintype "passive"))
      (node (ref "C28") (pin "2") (pinfunction "2_2") (pintype "passive"))
      (node (ref "C29") (pin "2") (pinfunction "2_2") (pintype "passive"))
      (node (ref "C3") (pin "2") (pinfunction "2_2") (pintype "passive"))
      (node (ref "C30") (pin "2") (pinfunction "2_2") (pintype "passive"))
      (node (ref "C31") (pin "2") (pinfunction "2_2") (pintype "passive"))
      (node (ref "C4") (pin "2") (pinfunction "2_2") (pintype "passive"))
      (node (ref "C5") (pin "2") (pinfunction "2_2") (pintype "passive"))
      (node (ref "C6") (pin "2") (pinfunction "2_2") (pintype "passive"))
      (node (ref "C7") (pin "2") (pinfunction "2_2") (pintype "passive"))
      (node (ref "C8") (pin "2") (pinfunction "2_2") (pintype "passive"))
      (node (ref "C9") (pin "2") (pinfunction "2_2") (pintype "passive"))
      (node (ref "D34L") (pin "A") (pinfunction "1_A") (pintype "bidirectional"))
      (node (ref "D34L") (pin "AA") (pinfunction "23_AA") (pintype "bidirectional"))
      (node (ref "D34L") (pin "C") (pinfunction "3_C") (pintype "bidirectional"))
      (node (ref "D34L") (pin "CC") (pinfunction "25_CC") (pintype "bidirectional"))
      (node (ref "D34L") (pin "E") (pinfunction "5_E") (pintype "bidirectional"))
      (node (ref "D34L") (pin "EE") (pinfunction "27_EE") (pintype "bidirectional"))
      (node (ref "D34L") (pin "H") (pinfunction "7_H") (pintype "bidirectional"))
      (node (ref "D34L") (pin "HH") (pinfunction "29_HH") (pintype "bidirectional"))
      (node (ref "D34L") (pin "K") (pinfunction "9_K") (pintype "bidirectional"))
      (node (ref "D34L") (pin "KK") (pinfunction "31_KK") (pintype "bidirectional"))
      (node (ref "D34L") (pin "M") (pinfunction "11_M") (pintype "bidirectional"))
      (node (ref "D34L") (pin "MM") (pinfunction "33_MM") (pintype "bidirectional"))
      (node (ref "D34L") (pin "P") (pinfunction "13_P") (pintype "bidirectional"))
      (node (ref "D34L") (pin "PP") (pinfunction "35_PP") (pintype "bidirectional"))
      (node (ref "D34L") (pin "S") (pinfunction "15_S") (pintype "bidirectional"))
      (node (ref "D34L") (pin "SS") (pinfunction "37_SS") (pintype "bidirectional"))
      (node (ref "D34L") (pin "U") (pinfunction "17_U") (pintype "bidirectional"))
      (node (ref "D34L") (pin "UU") (pinfunction "39_UU") (pintype "bidirectional"))
      (node (ref "D34L") (pin "W") (pinfunction "19_W") (pintype "bidirectional"))
      (node (ref "D34L") (pin "Y") (pinfunction "21_Y") (pintype "bidirectional"))
      (node (ref "D35L") (pin "A") (pinfunction "1_A") (pintype "bidirectional"))
      (node (ref "D35L") (pin "AA") (pinfunction "23_AA") (pintype "bidirectional"))
      (node (ref "D35L") (pin "C") (pinfunction "3_C") (pintype "bidirectional"))
      (node (ref "D35L") (pin "CC") (pinfunction "25_CC") (pintype "bidirectional"))
      (node (ref "D35L") (pin "E") (pinfunction "5_E") (pintype "bidirectional"))
      (node (ref "D35L") (pin "EE") (pinfunction "27_EE") (pintype "bidirectional"))
      (node (ref "D35L") (pin "H") (pinfunction "7_H") (pintype "bidirectional"))
      (node (ref "D35L") (pin "HH") (pinfunction "29_HH") (pintype "bidirectional"))
      (node (ref "D35L") (pin "K") (pinfunction "9_K") (pintype "bidirectional"))
      (node (ref "D35L") (pin "KK") (pinfunction "31_KK") (pintype "bidirectional"))
      (node (ref "D35L") (pin "M") (pinfunction "11_M") (pintype "bidirectional"))
      (node (ref "D35L") (pin "MM") (pinfunction "33_MM") (pintype "bidirectional"))
      (node (ref "D35L") (pin "P") (pinfunction "13_P") (pintype "bidirectional"))
      (node (ref "D35L") (pin "PP") (pinfunction "35_PP") (pintype "bidirectional"))
      (node (ref "D35L") (pin "S") (pinfunction "15_S") (pintype "bidirectional"))
      (node (ref "D35L") (pin "SS") (pinfunction "37_SS") (pintype "bidirectional"))
      (node (ref "D35L") (pin "U") (pinfunction "17_U") (pintype "bidirectional"))
      (node (ref "D35L") (pin "UU") (pinfunction "39_UU") (pintype "bidirectional"))
      (node (ref "D35L") (pin "W") (pinfunction "19_W") (pintype "bidirectional"))
      (node (ref "D35L") (pin "Y") (pinfunction "21_Y") (pintype "bidirectional"))
      (node (ref "D36L") (pin "A") (pinfunction "1_A") (pintype "bidirectional"))
      (node (ref "D36L") (pin "AA") (pinfunction "23_AA") (pintype "bidirectional"))
      (node (ref "D36L") (pin "C") (pinfunction "3_C") (pintype "bidirectional"))
      (node (ref "D36L") (pin "CC") (pinfunction "25_CC") (pintype "bidirectional"))
      (node (ref "D36L") (pin "E") (pinfunction "5_E") (pintype "bidirectional"))
      (node (ref "D36L") (pin "EE") (pinfunction "27_EE") (pintype "bidirectional"))
      (node (ref "D36L") (pin "H") (pinfunction "7_H") (pintype "bidirectional"))
      (node (ref "D36L") (pin "HH") (pinfunction "29_HH") (pintype "bidirectional"))
      (node (ref "D36L") (pin "K") (pinfunction "9_K") (pintype "bidirectional"))
      (node (ref "D36L") (pin "KK") (pinfunction "31_KK") (pintype "bidirectional"))
      (node (ref "D36L") (pin "M") (pinfunction "11_M") (pintype "bidirectional"))
      (node (ref "D36L") (pin "MM") (pinfunction "33_MM") (pintype "bidirectional"))
      (node (ref "D36L") (pin "P") (pinfunction "13_P") (pintype "bidirectional"))
      (node (ref "D36L") (pin "PP") (pinfunction "35_PP") (pintype "bidirectional"))
      (node (ref "D36L") (pin "S") (pinfunction "15_S") (pintype "bidirectional"))
      (node (ref "D36L") (pin "SS") (pinfunction "37_SS") (pintype "bidirectional"))
      (node (ref "D36L") (pin "U") (pinfunction "17_U") (pintype "bidirectional"))
      (node (ref "D36L") (pin "UU") (pinfunction "39_UU") (pintype "bidirectional"))
      (node (ref "D36L") (pin "W") (pinfunction "19_W") (pintype "bidirectional"))
      (node (ref "D36L") (pin "Y") (pinfunction "21_Y") (pintype "bidirectional"))
      (node (ref "D6") (pin "A") (pinfunction "A_A") (pintype "passive"))
      (node (ref "E1") (pin "1") (pinfunction "G_1") (pintype "input"))
      (node (ref "E1") (pin "19") (pinfunction "G_19") (pintype "input"))
      (node (ref "E10") (pin "11") (pinfunction "I_11") (pintype "input"))
      (node (ref "E13") (pin "4") (pinfunction "G2A_4") (pintype "input"))
      (node (ref "E13") (pin "5") (pinfunction "G2B_5") (pintype "input"))
      (node (ref "E14") (pin "4") (pinfunction "G2A_4") (pintype "input"))
      (node (ref "E14") (pin "5") (pinfunction "G2B_5") (pintype "input"))
      (node (ref "E15") (pin "4") (pinfunction "G2A_4") (pintype "input"))
      (node (ref "E15") (pin "5") (pinfunction "G2B_5") (pintype "input"))
      (node (ref "E16") (pin "4") (pinfunction "G2A_4") (pintype "input"))
      (node (ref "E16") (pin "5") (pinfunction "G2B_5") (pintype "input"))
      (node (ref "E2") (pin "12") (pinfunction "RES_12") (pintype "input"))
      (node (ref "E2") (pin "8") (pinfunction "VSS_8") (pintype "power_in"))
      (node (ref "E3") (pin "12") (pinfunction "RES_12") (pintype "input"))
      (node (ref "E3") (pin "8") (pinfunction "VSS_8") (pintype "power_in"))
      (node (ref "E4") (pin "6") (pinfunction "I0_6") (pintype "input"))
      (node (ref "E4") (pin "7") (pinfunction "I1_7") (pintype "input"))
      (node (ref "E5") (pin "16") (pinfunction "SFD_16") (pintype "input"))
      (node (ref "E5") (pin "4") (pinfunction "RRD_4") (pintype "input"))
      (node (ref "E7") (pin "12") (pinfunction "I0_12") (pintype "input"))
      (node (ref "E7") (pin "13") (pinfunction "I1_13") (pintype "input"))
      (node (ref "IC2") (pin "2") (pinfunction "GND_2") (pintype "passive"))
      (node (ref "IC3") (pin "1") (pinfunction "GND_1") (pintype "passive"))
      (node (ref "J1") (pin "5") (pinfunction "F_5") (pintype "passive"))
      (node (ref "J1") (pin "G1") (pinfunction "G1_G1") (pintype "passive"))
      (node (ref "J1") (pin "G2") (pinfunction "G2_G2") (pintype "passive"))
      (node (ref "LASTDEV") (pin "1") (pinfunction "1_1") (pintype "passive"))
      (node (ref "STOPB") (pin "1") (pinfunction "1_1") (pintype "passive"))
      (node (ref "X3") (pin "1") (pinfunction "KL_1") (pintype "passive"))
    )
    (net (code "46") (name "KB") (class "Default")
      (node (ref "E6") (pin "1") (pinfunction "O_1") (pintype "output"))
      (node (ref "E7") (pin "1") (pinfunction "I0_1") (pintype "input"))
      (node (ref "E8") (pin "1") (pinfunction "I0_1") (pintype "input"))
      (node (ref "E8") (pin "4") (pinfunction "I0_4") (pintype "input"))
    )
    (net (code "47") (name "KBF") (class "Default")
      (node (ref "E19") (pin "1") (pinfunction "I0_1") (pintype "input"))
      (node (ref "E23") (pin "6") (pinfunction "I0_6") (pintype "input"))
      (node (ref "E23") (pin "7") (pinfunction "I1_7") (pintype "input"))
      (node (ref "E5") (pin "19") (pinfunction "DR_19") (pintype "tri_state"))
    )
    (net (code "48") (name "KCC") (class "Default")
      (node (ref "E10") (pin "2") (pinfunction "O_2") (pintype "output"))
      (node (ref "E18") (pin "6") (pinfunction "I0_6") (pintype "input"))
      (node (ref "E18") (pin "7") (pinfunction "I1_7") (pintype "input"))
    )
    (net (code "49") (name "KRS") (class "Default")
      (node (ref "E17") (pin "2") (pinfunction "I1_2") (pintype "input"))
      (node (ref "E17") (pin "7") (pinfunction "I1_7") (pintype "input"))
      (node (ref "E18") (pin "2") (pinfunction "I1_2") (pintype "input"))
      (node (ref "E19") (pin "7") (pinfunction "I1_7") (pintype "input"))
      (node (ref "E20") (pin "2") (pinfunction "I1_2") (pintype "input"))
      (node (ref "E21") (pin "2") (pinfunction "I1_2") (pintype "input"))
      (node (ref "E21") (pin "7") (pinfunction "I1_7") (pintype "input"))
      (node (ref "E4") (pin "2") (pinfunction "I1_2") (pintype "input"))
      (node (ref "E8") (pin "6") (pinfunction "O_6") (pintype "output"))
    )
    (net (code "50") (name "KSF") (class "Default")
      (node (ref "E19") (pin "2") (pinfunction "I1_2") (pintype "input"))
      (node (ref "E8") (pin "3") (pinfunction "O_3") (pintype "output"))
    )
    (net (code "51") (name "MR") (class "Default")
      (node (ref "E10") (pin "4") (pinfunction "O_4") (pintype "output"))
      (node (ref "E5") (pin "21") (pinfunction "MR_21") (pintype "input"))
    )
    (net (code "52") (name "Net-(D5-PadA)") (class "Default")
      (node (ref "D5") (pin "A") (pinfunction "A_A") (pintype "passive"))
      (node (ref "D6") (pin "C") (pinfunction "C_C") (pintype "passive"))
      (node (ref "R13") (pin "2") (pinfunction "2_2") (pintype "passive"))
      (node (ref "R14") (pin "1") (pinfunction "1_1") (pintype "passive"))
    )
    (net (code "53") (name "Net-(E2A-P1)") (class "Default")
      (node (ref "C31") (pin "1") (pinfunction "1_1") (pintype "passive"))
      (node (ref "E2") (pin "11") (pinfunction "P1_11") (pintype "input"))
      (node (ref "R2") (pin "2") (pinfunction "2_2") (pintype "passive"))
      (node (ref "X1") (pin "2") (pinfunction "2_2") (pintype "passive"))
    )
    (net (code "54") (name "Net-(E2A-~{P0})") (class "Default")
      (node (ref "C30") (pin "1") (pinfunction "1_1") (pintype "passive"))
      (node (ref "E2") (pin "10") (pinfunction "~{P0}_10") (pintype "output"))
      (node (ref "R2") (pin "1") (pinfunction "1_1") (pintype "passive"))
      (node (ref "X1") (pin "1") (pinfunction "1_1") (pintype "passive"))
    )
    (net (code "55") (name "Net-(E3A-P1)") (class "Default")
      (node (ref "C29") (pin "1") (pinfunction "1_1") (pintype "passive"))
      (node (ref "E3") (pin "11") (pinfunction "P1_11") (pintype "input"))
      (node (ref "R1") (pin "2") (pinfunction "2_2") (pintype "passive"))
      (node (ref "X2") (pin "2") (pinfunction "2_2") (pintype "passive"))
    )
    (net (code "56") (name "Net-(E3A-~{P0})") (class "Default")
      (node (ref "C28") (pin "1") (pinfunction "1_1") (pintype "passive"))
      (node (ref "E3") (pin "10") (pinfunction "~{P0}_10") (pintype "output"))
      (node (ref "R1") (pin "1") (pinfunction "1_1") (pintype "passive"))
      (node (ref "X2") (pin "1") (pinfunction "1_1") (pintype "passive"))
    )
    (net (code "57") (name "Net-(E10C-O)") (class "Default")
      (node (ref "E10") (pin "6") (pinfunction "O_6") (pintype "output"))
      (node (ref "E11") (pin "11") (pinfunction "CLK_11") (pintype "input"))
    )
    (net (code "58") (name "Net-(E10D-O)") (class "Default")
      (node (ref "E10") (pin "8") (pinfunction "O_8") (pintype "output"))
      (node (ref "E6") (pin "12") (pinfunction "I1_12") (pintype "input"))
    )
    (net (code "59") (name "Net-(E10E-O)") (class "Default")
      (node (ref "E10") (pin "10") (pinfunction "O_10") (pintype "output"))
      (node (ref "E10") (pin "13") (pinfunction "I_13") (pintype "input"))
    )
    (net (code "60") (name "Net-(E10F-O)") (class "Default")
      (node (ref "E10") (pin "12") (pinfunction "O_12") (pintype "output"))
      (node (ref "E6") (pin "8") (pinfunction "I0_8") (pintype "input"))
      (node (ref "E6") (pin "9") (pinfunction "I1_9") (pintype "input"))
    )
    (net (code "61") (name "Net-(E11B-CLR)") (class "Default")
      (node (ref "E11") (pin "13") (pinfunction "CLR_13") (pintype "input"))
      (node (ref "E8") (pin "11") (pinfunction "O_11") (pintype "output"))
    )
    (net (code "62") (name "Net-(E12A-C1+)") (class "Default")
      (node (ref "C25") (pin "1") (pinfunction "1_1") (pintype "passive"))
      (node (ref "E12") (pin "1") (pinfunction "C1+_1") (pintype "bidirectional"))
    )
    (net (code "63") (name "Net-(E12A-C1-)") (class "Default")
      (node (ref "C25") (pin "2") (pinfunction "2_2") (pintype "passive"))
      (node (ref "E12") (pin "3") (pinfunction "C1-_3") (pintype "bidirectional"))
    )
    (net (code "64") (name "Net-(E12A-C2+)") (class "Default")
      (node (ref "C24") (pin "1") (pinfunction "1_1") (pintype "passive"))
      (node (ref "E12") (pin "4") (pinfunction "C2+_4") (pintype "bidirectional"))
    )
    (net (code "65") (name "Net-(E12A-C2-)") (class "Default")
      (node (ref "C24") (pin "2") (pinfunction "2_2") (pintype "passive"))
      (node (ref "E12") (pin "5") (pinfunction "C2-_5") (pintype "bidirectional"))
    )
    (net (code "66") (name "Net-(E12A-V+)") (class "Default")
      (node (ref "C27") (pin "1") (pinfunction "1_1") (pintype "passive"))
      (node (ref "E12") (pin "2") (pinfunction "V+_2") (pintype "bidirectional"))
    )
    (net (code "67") (name "Net-(E12A-V-)") (class "Default")
      (node (ref "C26") (pin "2") (pinfunction "2_2") (pintype "passive"))
      (node (ref "E12") (pin "6") (pinfunction "V-_6") (pintype "bidirectional"))
    )
    (net (code "68") (name "Net-(E13A-Y0)") (class "Default")
      (node (ref "E13") (pin "15") (pinfunction "Y0_15") (pintype "output"))
      (node (ref "P") (pin "1") (pinfunction "1_1") (pintype "passive"))
    )
    (net (code "69") (name "Net-(E13A-Y1)") (class "Default")
      (node (ref "E13") (pin "14") (pinfunction "Y1_14") (pintype "output"))
      (node (ref "P") (pin "3") (pinfunction "3_3") (pintype "passive"))
    )
    (net (code "70") (name "Net-(E13A-Y2)") (class "Default")
      (node (ref "E13") (pin "13") (pinfunction "Y2_13") (pintype "output"))
      (node (ref "P") (pin "5") (pinfunction "5_5") (pintype "passive"))
    )
    (net (code "71") (name "Net-(E13A-Y3)") (class "Default")
      (node (ref "E13") (pin "12") (pinfunction "Y3_12") (pintype "output"))
      (node (ref "P") (pin "7") (pinfunction "7_7") (pintype "passive"))
    )
    (net (code "72") (name "Net-(E13A-Y4)") (class "Default")
      (node (ref "E13") (pin "11") (pinfunction "Y4_11") (pintype "output"))
      (node (ref "P") (pin "9") (pinfunction "9_9") (pintype "passive"))
    )
    (net (code "73") (name "Net-(E13A-Y5)") (class "Default")
      (node (ref "E13") (pin "10") (pinfunction "Y5_10") (pintype "output"))
      (node (ref "P") (pin "11") (pinfunction "11_11") (pintype "passive"))
    )
    (net (code "74") (name "Net-(E13A-Y6)") (class "Default")
      (node (ref "E13") (pin "9") (pinfunction "Y6_9") (pintype "output"))
      (node (ref "P") (pin "13") (pinfunction "13_13") (pintype "passive"))
    )
    (net (code "75") (name "Net-(E13A-Y7)") (class "Default")
      (node (ref "E13") (pin "7") (pinfunction "Y7_7") (pintype "output"))
      (node (ref "P") (pin "15") (pinfunction "15_15") (pintype "passive"))
    )
    (net (code "76") (name "Net-(E14A-Y0)") (class "Default")
      (node (ref "E14") (pin "15") (pinfunction "Y0_15") (pintype "output"))
      (node (ref "T") (pin "1") (pinfunction "1_1") (pintype "passive"))
    )
    (net (code "77") (name "Net-(E14A-Y1)") (class "Default")
      (node (ref "E14") (pin "14") (pinfunction "Y1_14") (pintype "output"))
      (node (ref "T") (pin "3") (pinfunction "3_3") (pintype "passive"))
    )
    (net (code "78") (name "Net-(E14A-Y2)") (class "Default")
      (node (ref "E14") (pin "13") (pinfunction "Y2_13") (pintype "output"))
      (node (ref "T") (pin "5") (pinfunction "5_5") (pintype "passive"))
    )
    (net (code "79") (name "Net-(E14A-Y3)") (class "Default")
      (node (ref "E14") (pin "12") (pinfunction "Y3_12") (pintype "output"))
      (node (ref "T") (pin "7") (pinfunction "7_7") (pintype "passive"))
    )
    (net (code "80") (name "Net-(E14A-Y4)") (class "Default")
      (node (ref "E14") (pin "11") (pinfunction "Y4_11") (pintype "output"))
      (node (ref "T") (pin "9") (pinfunction "9_9") (pintype "passive"))
    )
    (net (code "81") (name "Net-(E14A-Y5)") (class "Default")
      (node (ref "E14") (pin "10") (pinfunction "Y5_10") (pintype "output"))
      (node (ref "T") (pin "11") (pinfunction "11_11") (pintype "passive"))
    )
    (net (code "82") (name "Net-(E14A-Y6)") (class "Default")
      (node (ref "E14") (pin "9") (pinfunction "Y6_9") (pintype "output"))
      (node (ref "T") (pin "13") (pinfunction "13_13") (pintype "passive"))
    )
    (net (code "83") (name "Net-(E14A-Y7)") (class "Default")
      (node (ref "E14") (pin "7") (pinfunction "Y7_7") (pintype "output"))
      (node (ref "T") (pin "15") (pinfunction "15_15") (pintype "passive"))
    )
    (net (code "84") (name "Net-(E15A-Y0)") (class "Default")
      (node (ref "E15") (pin "15") (pinfunction "Y0_15") (pintype "output"))
      (node (ref "K") (pin "1") (pinfunction "1_1") (pintype "passive"))
    )
    (net (code "85") (name "Net-(E15A-Y1)") (class "Default")
      (node (ref "E15") (pin "14") (pinfunction "Y1_14") (pintype "output"))
      (node (ref "K") (pin "3") (pinfunction "3_3") (pintype "passive"))
    )
    (net (code "86") (name "Net-(E15A-Y2)") (class "Default")
      (node (ref "E15") (pin "13") (pinfunction "Y2_13") (pintype "output"))
      (node (ref "K") (pin "5") (pinfunction "5_5") (pintype "passive"))
    )
    (net (code "87") (name "Net-(E15A-Y3)") (class "Default")
      (node (ref "E15") (pin "12") (pinfunction "Y3_12") (pintype "output"))
      (node (ref "K") (pin "7") (pinfunction "7_7") (pintype "passive"))
    )
    (net (code "88") (name "Net-(E15A-Y4)") (class "Default")
      (node (ref "E15") (pin "11") (pinfunction "Y4_11") (pintype "output"))
      (node (ref "K") (pin "9") (pinfunction "9_9") (pintype "passive"))
    )
    (net (code "89") (name "Net-(E15A-Y5)") (class "Default")
      (node (ref "E15") (pin "10") (pinfunction "Y5_10") (pintype "output"))
      (node (ref "K") (pin "11") (pinfunction "11_11") (pintype "passive"))
    )
    (net (code "90") (name "Net-(E15A-Y6)") (class "Default")
      (node (ref "E15") (pin "9") (pinfunction "Y6_9") (pintype "output"))
      (node (ref "K") (pin "13") (pinfunction "13_13") (pintype "passive"))
    )
    (net (code "91") (name "Net-(E15A-Y7)") (class "Default")
      (node (ref "E15") (pin "7") (pinfunction "Y7_7") (pintype "output"))
      (node (ref "K") (pin "15") (pinfunction "15_15") (pintype "passive"))
    )
    (net (code "92") (name "Net-(E16A-Y0)") (class "Default")
      (node (ref "B") (pin "1") (pinfunction "1_1") (pintype "passive"))
      (node (ref "E16") (pin "15") (pinfunction "Y0_15") (pintype "output"))
    )
    (net (code "93") (name "Net-(E16A-Y1)") (class "Default")
      (node (ref "B") (pin "3") (pinfunction "3_3") (pintype "passive"))
      (node (ref "E16") (pin "14") (pinfunction "Y1_14") (pintype "output"))
    )
    (net (code "94") (name "Net-(E16A-Y2)") (class "Default")
      (node (ref "B") (pin "5") (pinfunction "5_5") (pintype "passive"))
      (node (ref "E16") (pin "13") (pinfunction "Y2_13") (pintype "output"))
    )
    (net (code "95") (name "Net-(E16A-Y3)") (class "Default")
      (node (ref "B") (pin "7") (pinfunction "7_7") (pintype "passive"))
      (node (ref "E16") (pin "12") (pinfunction "Y3_12") (pintype "output"))
    )
    (net (code "96") (name "Net-(E16A-Y4)") (class "Default")
      (node (ref "B") (pin "9") (pinfunction "9_9") (pintype "passive"))
      (node (ref "E16") (pin "11") (pinfunction "Y4_11") (pintype "output"))
    )
    (net (code "97") (name "Net-(E16A-Y5)") (class "Default")
      (node (ref "B") (pin "11") (pinfunction "11_11") (pintype "passive"))
      (node (ref "E16") (pin "10") (pinfunction "Y5_10") (pintype "output"))
    )
    (net (code "98") (name "Net-(E16A-Y6)") (class "Default")
      (node (ref "B") (pin "13") (pinfunction "13_13") (pintype "passive"))
      (node (ref "E16") (pin "9") (pinfunction "Y6_9") (pintype "output"))
    )
    (net (code "99") (name "Net-(E16A-Y7)") (class "Default")
      (node (ref "B") (pin "15") (pinfunction "15_15") (pintype "passive"))
      (node (ref "E16") (pin "7") (pinfunction "Y7_7") (pintype "output"))
    )
    (net (code "100") (name "Net-(PAD1-P)") (class "Default")
      (node (ref "E9") (pin "1") (pinfunction "1_1") (pintype "passive"))
      (node (ref "PAD1") (pin "1") (pinfunction "P_1") (pintype "passive"))
    )
    (net (code "101") (name "Net-(PAD2-P)") (class "Default")
      (node (ref "E9") (pin "2") (pinfunction "2_2") (pintype "passive"))
      (node (ref "PAD2") (pin "1") (pinfunction "P_1") (pintype "passive"))
    )
    (net (code "102") (name "Net-(PAD3-P)") (class "Default")
      (node (ref "E9") (pin "3") (pinfunction "3_3") (pintype "passive"))
      (node (ref "PAD3") (pin "1") (pinfunction "P_1") (pintype "passive"))
    )
    (net (code "103") (name "Net-(PAD4-P)") (class "Default")
      (node (ref "E9") (pin "4") (pinfunction "4_4") (pintype "passive"))
      (node (ref "PAD4") (pin "1") (pinfunction "P_1") (pintype "passive"))
    )
    (net (code "104") (name "Net-(PAD5-P)") (class "Default")
      (node (ref "E9") (pin "5") (pinfunction "5_5") (pintype "passive"))
      (node (ref "PAD5") (pin "1") (pinfunction "P_1") (pintype "passive"))
    )
    (net (code "105") (name "Net-(PAD6-P)") (class "Default")
      (node (ref "E9") (pin "6") (pinfunction "6_6") (pintype "passive"))
      (node (ref "PAD6") (pin "1") (pinfunction "P_1") (pintype "passive"))
    )
    (net (code "106") (name "Net-(PAD7-P)") (class "Default")
      (node (ref "E9") (pin "7") (pinfunction "7_7") (pintype "passive"))
      (node (ref "PAD7") (pin "1") (pinfunction "P_1") (pintype "passive"))
    )
    (net (code "107") (name "Net-(PAD8-P)") (class "Default")
      (node (ref "E9") (pin "8") (pinfunction "8_8") (pintype "passive"))
      (node (ref "PAD8") (pin "1") (pinfunction "P_1") (pintype "passive"))
    )
    (net (code "108") (name "Net-(PAD9-P)") (class "Default")
      (node (ref "E9") (pin "16") (pinfunction "16_16") (pintype "passive"))
      (node (ref "PAD9") (pin "1") (pinfunction "P_1") (pintype "passive"))
    )
    (net (code "109") (name "Net-(PAD18-P)") (class "Default")
      (node (ref "E22") (pin "1") (pinfunction "1_1") (pintype "passive"))
      (node (ref "PAD18") (pin "1") (pinfunction "P_1") (pintype "passive"))
    )
    (net (code "110") (name "Net-(PAD19-P)") (class "Default")
      (node (ref "E22") (pin "2") (pinfunction "2_2") (pintype "passive"))
      (node (ref "PAD19") (pin "1") (pinfunction "P_1") (pintype "passive"))
    )
    (net (code "111") (name "Net-(PAD28-P)") (class "Default")
      (node (ref "E22") (pin "3") (pinfunction "3_3") (pintype "passive"))
      (node (ref "PAD28") (pin "1") (pinfunction "P_1") (pintype "passive"))
    )
    (net (code "112") (name "Net-(PAD29-P)") (class "Default")
      (node (ref "E22") (pin "4") (pinfunction "4_4") (pintype "passive"))
      (node (ref "PAD29") (pin "1") (pinfunction "P_1") (pintype "passive"))
    )
    (net (code "113") (name "Net-(PAD30-P)") (class "Default")
      (node (ref "E22") (pin "5") (pinfunction "5_5") (pintype "passive"))
      (node (ref "PAD30") (pin "1") (pinfunction "P_1") (pintype "passive"))
    )
    (net (code "114") (name "Net-(PAD31-P)") (class "Default")
      (node (ref "E22") (pin "6") (pinfunction "6_6") (pintype "passive"))
      (node (ref "PAD31") (pin "1") (pinfunction "P_1") (pintype "passive"))
    )
    (net (code "115") (name "Net-(PAD32-P)") (class "Default")
      (node (ref "E22") (pin "7") (pinfunction "7_7") (pintype "passive"))
      (node (ref "PAD32") (pin "1") (pinfunction "P_1") (pintype "passive"))
    )
    (net (code "116") (name "Net-(PAD33-P)") (class "Default")
      (node (ref "E22") (pin "8") (pinfunction "8_8") (pintype "passive"))
      (node (ref "PAD33") (pin "1") (pinfunction "P_1") (pintype "passive"))
    )
    (net (code "117") (name "Net-(PAD34-P)") (class "Default")
      (node (ref "E22") (pin "16") (pinfunction "16_16") (pintype "passive"))
      (node (ref "PAD34") (pin "1") (pinfunction "P_1") (pintype "passive"))
    )
    (net (code "118") (name "Net-(PAD35-P)") (class "Default")
      (node (ref "E22") (pin "15") (pinfunction "15_15") (pintype "passive"))
      (node (ref "PAD35") (pin "1") (pinfunction "P_1") (pintype "passive"))
    )
    (net (code "119") (name "Net-(PAD36-P)") (class "Default")
      (node (ref "E22") (pin "14") (pinfunction "14_14") (pintype "passive"))
      (node (ref "PAD36") (pin "1") (pinfunction "P_1") (pintype "passive"))
    )
    (net (code "120") (name "Net-(PAD37-P)") (class "Default")
      (node (ref "E22") (pin "13") (pinfunction "13_13") (pintype "passive"))
      (node (ref "PAD37") (pin "1") (pinfunction "P_1") (pintype "passive"))
    )
    (net (code "121") (name "Net-(PAD38-P)") (class "Default")
      (node (ref "E22") (pin "12") (pinfunction "12_12") (pintype "passive"))
      (node (ref "PAD38") (pin "1") (pinfunction "P_1") (pintype "passive"))
    )
    (net (code "122") (name "Net-(PAD39-P)") (class "Default")
      (node (ref "E22") (pin "11") (pinfunction "11_11") (pintype "passive"))
      (node (ref "PAD39") (pin "1") (pinfunction "P_1") (pintype "passive"))
    )
    (net (code "123") (name "Net-(PAD40-P)") (class "Default")
      (node (ref "E22") (pin "10") (pinfunction "10_10") (pintype "passive"))
      (node (ref "PAD40") (pin "1") (pinfunction "P_1") (pintype "passive"))
    )
    (net (code "124") (name "Net-(PAD41-P)") (class "Default")
      (node (ref "E22") (pin "9") (pinfunction "9_9") (pintype "passive"))
      (node (ref "PAD41") (pin "1") (pinfunction "P_1") (pintype "passive"))
    )
    (net (code "125") (name "Net-(PAD42-P)") (class "Default")
      (node (ref "E9") (pin "15") (pinfunction "15_15") (pintype "passive"))
      (node (ref "PAD42") (pin "1") (pinfunction "P_1") (pintype "passive"))
    )
    (net (code "126") (name "Net-(PAD43-P)") (class "Default")
      (node (ref "E9") (pin "14") (pinfunction "14_14") (pintype "passive"))
      (node (ref "PAD43") (pin "1") (pinfunction "P_1") (pintype "passive"))
    )
    (net (code "127") (name "Net-(PAD44-P)") (class "Default")
      (node (ref "E9") (pin "13") (pinfunction "13_13") (pintype "passive"))
      (node (ref "PAD44") (pin "1") (pinfunction "P_1") (pintype "passive"))
    )
    (net (code "128") (name "Net-(PAD45-P)") (class "Default")
      (node (ref "E9") (pin "12") (pinfunction "12_12") (pintype "passive"))
      (node (ref "PAD45") (pin "1") (pinfunction "P_1") (pintype "passive"))
    )
    (net (code "129") (name "Net-(PAD46-P)") (class "Default")
      (node (ref "E9") (pin "11") (pinfunction "11_11") (pintype "passive"))
      (node (ref "PAD46") (pin "1") (pinfunction "P_1") (pintype "passive"))
    )
    (net (code "130") (name "Net-(PAD47-P)") (class "Default")
      (node (ref "E9") (pin "10") (pinfunction "10_10") (pintype "passive"))
      (node (ref "PAD47") (pin "1") (pinfunction "P_1") (pintype "passive"))
    )
    (net (code "131") (name "Net-(PAD48-P)") (class "Default")
      (node (ref "E9") (pin "9") (pinfunction "9_9") (pintype "passive"))
      (node (ref "PAD48") (pin "1") (pinfunction "P_1") (pintype "passive"))
    )
    (net (code "132") (name "Net-(Q1-B)") (class "Default")
      (node (ref "Q1") (pin "2") (pinfunction "B_2") (pintype "passive"))
      (node (ref "R5") (pin "2") (pinfunction "2_2") (pintype "passive"))
    )
    (net (code "133") (name "Net-(Q1-C)") (class "Default")
      (node (ref "D1") (pin "A") (pinfunction "A_A") (pintype "passive"))
      (node (ref "Q1") (pin "3") (pinfunction "C_3") (pintype "passive"))
      (node (ref "R3") (pin "2") (pinfunction "2_2") (pintype "passive"))
    )
    (net (code "134") (name "Net-(Q2-B)") (class "Default")
      (node (ref "Q2") (pin "2") (pinfunction "B_2") (pintype "passive"))
      (node (ref "R7") (pin "2") (pinfunction "2_2") (pintype "passive"))
    )
    (net (code "135") (name "Net-(Q2-C)") (class "Default")
      (node (ref "D3") (pin "A") (pinfunction "A_A") (pintype "passive"))
      (node (ref "Q2") (pin "3") (pinfunction "C_3") (pintype "passive"))
      (node (ref "R8") (pin "2") (pinfunction "2_2") (pintype "passive"))
    )
    (net (code "136") (name "PT") (class "Default")
      (node (ref "E6") (pin "4") (pinfunction "O_4") (pintype "output"))
      (node (ref "E7") (pin "4") (pinfunction "I0_4") (pintype "input"))
      (node (ref "E7") (pin "9") (pinfunction "I0_9") (pintype "input"))
      (node (ref "E8") (pin "9") (pinfunction "I0_9") (pintype "input"))
    )
    (net (code "137") (name "RBR1") (class "Default")
      (node (ref "E20") (pin "1") (pinfunction "I0_1") (pintype "input"))
      (node (ref "E5") (pin "12") (pinfunction "RBR1_12") (pintype "tri_state"))
    )
    (net (code "138") (name "RBR2") (class "Default")
      (node (ref "E21") (pin "6") (pinfunction "I0_6") (pintype "input"))
      (node (ref "E5") (pin "11") (pinfunction "RBR2_11") (pintype "tri_state"))
    )
    (net (code "139") (name "RBR3") (class "Default")
      (node (ref "E21") (pin "1") (pinfunction "I0_1") (pintype "input"))
      (node (ref "E5") (pin "10") (pinfunction "RBR3_10") (pintype "tri_state"))
    )
    (net (code "140") (name "RBR4") (class "Default")
      (node (ref "E4") (pin "1") (pinfunction "I0_1") (pintype "input"))
      (node (ref "E5") (pin "9") (pinfunction "RBR4_9") (pintype "tri_state"))
    )
    (net (code "141") (name "RBR5") (class "Default")
      (node (ref "E17") (pin "6") (pinfunction "I0_6") (pintype "input"))
      (node (ref "E5") (pin "8") (pinfunction "RBR5_8") (pintype "tri_state"))
    )
    (net (code "142") (name "RBR6") (class "Default")
      (node (ref "E17") (pin "1") (pinfunction "I0_1") (pintype "input"))
      (node (ref "E5") (pin "7") (pinfunction "RBR6_7") (pintype "tri_state"))
    )
    (net (code "143") (name "RBR7") (class "Default")
      (node (ref "E18") (pin "1") (pinfunction "I0_1") (pintype "input"))
      (node (ref "E5") (pin "6") (pinfunction "RBR7_6") (pintype "tri_state"))
    )
    (net (code "144") (name "RBR8") (class "Default")
      (node (ref "E19") (pin "6") (pinfunction "I0_6") (pintype "input"))
      (node (ref "E5") (pin "5") (pinfunction "RBR8_5") (pintype "tri_state"))
    )
    (net (code "145") (name "RRUN") (class "Default")
      (node (ref "E11") (pin "8") (pinfunction "~{Q}_8") (pintype "output"))
      (node (ref "E12") (pin "10") (pinfunction "T2IN_10") (pintype "input"))
      (node (ref "R7") (pin "1") (pinfunction "1_1") (pintype "passive"))
    )
    (net (code "146") (name "RRUN+") (class "Default")
      (node (ref "D3") (pin "C") (pinfunction "C_C") (pintype "passive"))
      (node (ref "D4") (pin "C") (pinfunction "C_C") (pintype "passive"))
      (node (ref "R10") (pin "2") (pinfunction "2_2") (pintype "passive"))
      (node (ref "X3") (pin "6") (pinfunction "KL_6") (pintype "passive"))
    )
    (net (code "147") (name "RRUN-") (class "Default")
      (node (ref "R9") (pin "2") (pinfunction "2_2") (pintype "passive"))
      (node (ref "X3") (pin "4") (pinfunction "KL_4") (pintype "passive"))
    )
    (net (code "148") (name "RTS") (class "Default")
      (node (ref "E12") (pin "7") (pinfunction "T2OUT_7") (pintype "output"))
      (node (ref "E12") (pin "8") (pinfunction "R2IN_8") (pintype "input"))
      (node (ref "J1") (pin "8") (pinfunction "F_8") (pintype "passive"))
    )
    (net (code "149") (name "RX") (class "Default")
      (node (ref "E10") (pin "5") (pinfunction "I_5") (pintype "input"))
      (node (ref "E5") (pin "20") (pinfunction "RRI_20") (pintype "input"))
      (node (ref "E6") (pin "13") (pinfunction "O_13") (pintype "output"))
    )
    (net (code "150") (name "RX+") (class "Default")
      (node (ref "R11") (pin "1") (pinfunction "1_1") (pintype "passive"))
      (node (ref "R13") (pin "1") (pinfunction "1_1") (pintype "passive"))
      (node (ref "X3") (pin "7") (pinfunction "KL_7") (pintype "passive"))
    )
    (net (code "151") (name "RX-") (class "Default")
      (node (ref "R12") (pin "2") (pinfunction "2_2") (pintype "passive"))
      (node (ref "X3") (pin "3") (pinfunction "KL_3") (pintype "passive"))
    )
    (net (code "152") (name "RXD") (class "Default")
      (node (ref "E12") (pin "13") (pinfunction "R1IN_13") (pintype "input"))
      (node (ref "J1") (pin "3") (pinfunction "F_3") (pintype "passive"))
    )
    (net (code "153") (name "RXE") (class "Default")
      (node (ref "E10") (pin "9") (pinfunction "I_9") (pintype "input"))
      (node (ref "E12") (pin "12") (pinfunction "R1OUT_12") (pintype "output"))
    )
    (net (code "154") (name "STOPB") (class "Default")
      (node (ref "E5") (pin "36") (pinfunction "SBS_36") (pintype "input"))
      (node (ref "STOPB") (pin "2") (pinfunction "2_2") (pintype "passive"))
    )
    (net (code "155") (name "TBR1") (class "Default")
      (node (ref "E1") (pin "18") (pinfunction "Y1_18") (pintype "tri_state"))
      (node (ref "E5") (pin "26") (pinfunction "TBR1_26") (pintype "input"))
    )
    (net (code "156") (name "TBR2") (class "Default")
      (node (ref "E1") (pin "16") (pinfunction "Y2_16") (pintype "tri_state"))
      (node (ref "E5") (pin "27") (pinfunction "TBR2_27") (pintype "input"))
    )
    (net (code "157") (name "TBR3") (class "Default")
      (node (ref "E1") (pin "14") (pinfunction "Y3_14") (pintype "tri_state"))
      (node (ref "E5") (pin "28") (pinfunction "TBR3_28") (pintype "input"))
    )
    (net (code "158") (name "TBR4") (class "Default")
      (node (ref "E1") (pin "12") (pinfunction "Y4_12") (pintype "tri_state"))
      (node (ref "E5") (pin "29") (pinfunction "TBR4_29") (pintype "input"))
    )
    (net (code "159") (name "TBR5") (class "Default")
      (node (ref "E1") (pin "9") (pinfunction "Y1_9") (pintype "tri_state"))
      (node (ref "E5") (pin "30") (pinfunction "TBR5_30") (pintype "input"))
    )
    (net (code "160") (name "TBR6") (class "Default")
      (node (ref "E1") (pin "7") (pinfunction "Y2_7") (pintype "tri_state"))
      (node (ref "E5") (pin "31") (pinfunction "TBR6_31") (pintype "input"))
    )
    (net (code "161") (name "TBR7") (class "Default")
      (node (ref "E1") (pin "5") (pinfunction "Y3_5") (pintype "tri_state"))
      (node (ref "E5") (pin "32") (pinfunction "TBR7_32") (pintype "input"))
    )
    (net (code "162") (name "TBR8") (class "Default")
      (node (ref "E1") (pin "3") (pinfunction "Y4_3") (pintype "tri_state"))
      (node (ref "E5") (pin "33") (pinfunction "TBR8_33") (pintype "input"))
    )
    (net (code "163") (name "TPF") (class "Default")
      (node (ref "E11") (pin "5") (pinfunction "Q_5") (pintype "output"))
      (node (ref "E20") (pin "6") (pinfunction "I0_6") (pintype "input"))
      (node (ref "E23") (pin "1") (pinfunction "I0_1") (pintype "input"))
      (node (ref "E23") (pin "2") (pinfunction "I1_2") (pintype "input"))
    )
    (net (code "164") (name "TRE") (class "Default")
      (node (ref "E11") (pin "3") (pinfunction "CLK_3") (pintype "input"))
      (node (ref "E5") (pin "24") (pinfunction "TRE_24") (pintype "output"))
    )
    (net (code "165") (name "TSF") (class "Default")
      (node (ref "E20") (pin "7") (pinfunction "I1_7") (pintype "input"))
      (node (ref "E8") (pin "8") (pinfunction "O_8") (pintype "output"))
    )
    (net (code "166") (name "TX") (class "Default")
      (node (ref "E12") (pin "11") (pinfunction "T1IN_11") (pintype "input"))
      (node (ref "E5") (pin "25") (pinfunction "TRO_25") (pintype "output"))
      (node (ref "R5") (pin "1") (pinfunction "1_1") (pintype "passive"))
    )
    (net (code "167") (name "TX+") (class "Default")
      (node (ref "D1") (pin "C") (pinfunction "C_C") (pintype "passive"))
      (node (ref "D2") (pin "C") (pinfunction "C_C") (pintype "passive"))
      (node (ref "R6") (pin "2") (pinfunction "2_2") (pintype "passive"))
      (node (ref "X3") (pin "5") (pinfunction "KL_5") (pintype "passive"))
    )
    (net (code "168") (name "TX-") (class "Default")
      (node (ref "R4") (pin "2") (pinfunction "2_2") (pintype "passive"))
      (node (ref "X3") (pin "2") (pinfunction "KL_2") (pintype "passive"))
    )
    (net (code "169") (name "TXD") (class "Default")
      (node (ref "E12") (pin "14") (pinfunction "T1OUT_14") (pintype "output"))
      (node (ref "J1") (pin "2") (pinfunction "F_2") (pintype "passive"))
    )
    (net (code "170") (name "VCC") (class "Default")
      (node (ref "5/8") (pin "3") (pinfunction "3_3") (pintype "passive"))
      (node (ref "C1") (pin "1") (pinfunction "1_1") (pintype "passive"))
      (node (ref "C10") (pin "1") (pinfunction "1_1") (pintype "passive"))
      (node (ref "C11") (pin "1") (pinfunction "1_1") (pintype "passive"))
      (node (ref "C12") (pin "1") (pinfunction "1_1") (pintype "passive"))
      (node (ref "C13") (pin "1") (pinfunction "1_1") (pintype "passive"))
      (node (ref "C14") (pin "1") (pinfunction "1_1") (pintype "passive"))
      (node (ref "C15") (pin "1") (pinfunction "1_1") (pintype "passive"))
      (node (ref "C16") (pin "1") (pinfunction "1_1") (pintype "passive"))
      (node (ref "C17") (pin "1") (pinfunction "1_1") (pintype "passive"))
      (node (ref "C18") (pin "1") (pinfunction "1_1") (pintype "passive"))
      (node (ref "C19") (pin "1") (pinfunction "1_1") (pintype "passive"))
      (node (ref "C2") (pin "1") (pinfunction "1_1") (pintype "passive"))
      (node (ref "C20") (pin "1") (pinfunction "1_1") (pintype "passive"))
      (node (ref "C21") (pin "1") (pinfunction "1_1") (pintype "passive"))
      (node (ref "C22") (pin "1") (pinfunction "1_1") (pintype "passive"))
      (node (ref "C23") (pin "+") (pinfunction "+_+") (pintype "passive"))
      (node (ref "C27") (pin "2") (pinfunction "2_2") (pintype "passive"))
      (node (ref "C3") (pin "1") (pinfunction "1_1") (pintype "passive"))
      (node (ref "C4") (pin "1") (pinfunction "1_1") (pintype "passive"))
      (node (ref "C5") (pin "1") (pinfunction "1_1") (pintype "passive"))
      (node (ref "C6") (pin "1") (pinfunction "1_1") (pintype "passive"))
      (node (ref "C7") (pin "1") (pinfunction "1_1") (pintype "passive"))
      (node (ref "C8") (pin "1") (pinfunction "1_1") (pintype "passive"))
      (node (ref "C9") (pin "1") (pinfunction "1_1") (pintype "passive"))
      (node (ref "D5") (pin "C") (pinfunction "C_C") (pintype "passive"))
      (node (ref "E11") (pin "10") (pinfunction "PRE_10") (pintype "input"))
      (node (ref "E11") (pin "12") (pinfunction "D_12") (pintype "input"))
      (node (ref "E11") (pin "2") (pinfunction "D_2") (pintype "input"))
      (node (ref "E11") (pin "4") (pinfunction "PRE_4") (pintype "input"))
      (node (ref "E13") (pin "6") (pinfunction "G1_6") (pintype "input"))
      (node (ref "E14") (pin "6") (pinfunction "G1_6") (pintype "input"))
      (node (ref "E15") (pin "6") (pinfunction "G1_6") (pintype "input"))
      (node (ref "E16") (pin "6") (pinfunction "G1_6") (pintype "input"))
      (node (ref "E2") (pin "16") (pinfunction "VDD_16") (pintype "power_in"))
      (node (ref "E3") (pin "16") (pinfunction "VDD_16") (pintype "power_in"))
      (node (ref "E5") (pin "34") (pinfunction "CRL_34") (pintype "input"))
      (node (ref "E5") (pin "35") (pinfunction "PI_35") (pintype "input"))
      (node (ref "E5") (pin "39") (pinfunction "EPE_39") (pintype "input"))
      (node (ref "IC2") (pin "3") (pinfunction "VO_3") (pintype "passive"))
      (node (ref "Q1") (pin "1") (pinfunction "E_1") (pintype "passive"))
      (node (ref "Q2") (pin "1") (pinfunction "E_1") (pintype "passive"))
      (node (ref "R11") (pin "2") (pinfunction "2_2") (pintype "passive"))
      (node (ref "STOPB") (pin "3") (pinfunction "3_3") (pintype "passive"))
    )
    (net (code "171") (name "unconnected-(D34L-2-PadB)") (class "Default")
      (node (ref "D34L") (pin "B") (pinfunction "2_B") (pintype "bidirectional"))
    )
    (net (code "172") (name "unconnected-(D34L-34-PadNN)") (class "Default")
      (node (ref "D34L") (pin "NN") (pinfunction "34_NN") (pintype "bidirectional"))
    )
    (net (code "173") (name "unconnected-(D34L-38-PadTT)") (class "Default")
      (node (ref "D34L") (pin "TT") (pinfunction "38_TT") (pintype "bidirectional"))
    )
    (net (code "174") (name "unconnected-(D34L-40-PadVV)") (class "Default")
      (node (ref "D34L") (pin "VV") (pinfunction "40_VV") (pintype "bidirectional"))
    )
    (net (code "175") (name "unconnected-(D35L-2-PadB)") (class "Default")
      (node (ref "D35L") (pin "B") (pinfunction "2_B") (pintype "bidirectional"))
    )
    (net (code "176") (name "unconnected-(D35L-40-PadVV)") (class "Default")
      (node (ref "D35L") (pin "VV") (pinfunction "40_VV") (pintype "bidirectional"))
    )
    (net (code "177") (name "unconnected-(D36L-2-PadB)") (class "Default")
      (node (ref "D36L") (pin "B") (pinfunction "2_B") (pintype "bidirectional"))
    )
    (net (code "178") (name "unconnected-(D36L-40-PadVV)") (class "Default")
      (node (ref "D36L") (pin "VV") (pinfunction "40_VV") (pintype "bidirectional"))
    )
    (net (code "179") (name "unconnected-(E2A-P0-Pad9)") (class "Default")
      (node (ref "E2") (pin "9") (pinfunction "P0_9") (pintype "output"))
    )
    (net (code "180") (name "unconnected-(E2A-Q12-Pad1)") (class "Default")
      (node (ref "E2") (pin "1") (pinfunction "Q12_1") (pintype "output"))
    )
    (net (code "181") (name "unconnected-(E2A-Q13-Pad2)") (class "Default")
      (node (ref "E2") (pin "2") (pinfunction "Q13_2") (pintype "output"))
    )
    (net (code "182") (name "unconnected-(E2A-Q14-Pad3)") (class "Default")
      (node (ref "E2") (pin "3") (pinfunction "Q14_3") (pintype "output"))
    )
    (net (code "183") (name "unconnected-(E3A-P0-Pad9)") (class "Default")
      (node (ref "E3") (pin "9") (pinfunction "P0_9") (pintype "output"))
    )
    (net (code "184") (name "unconnected-(E3A-Q4-Pad7)") (class "Default")
      (node (ref "E3") (pin "7") (pinfunction "Q4_7") (pintype "output"))
    )
    (net (code "185") (name "unconnected-(E3A-Q5-Pad5)") (class "Default")
      (node (ref "E3") (pin "5") (pinfunction "Q5_5") (pintype "output"))
    )
    (net (code "186") (name "unconnected-(E3A-Q6-Pad4)") (class "Default")
      (node (ref "E3") (pin "4") (pinfunction "Q6_4") (pintype "output"))
    )
    (net (code "187") (name "unconnected-(E3A-Q7-Pad6)") (class "Default")
      (node (ref "E3") (pin "6") (pinfunction "Q7_6") (pintype "output"))
    )
    (net (code "188") (name "unconnected-(E3A-Q8-Pad14)") (class "Default")
      (node (ref "E3") (pin "14") (pinfunction "Q8_14") (pintype "output"))
    )
    (net (code "189") (name "unconnected-(E3A-Q9-Pad13)") (class "Default")
      (node (ref "E3") (pin "13") (pinfunction "Q9_13") (pintype "output"))
    )
    (net (code "190") (name "unconnected-(E3A-Q10-Pad15)") (class "Default")
      (node (ref "E3") (pin "15") (pinfunction "Q10_15") (pintype "output"))
    )
    (net (code "191") (name "unconnected-(E3A-Q13-Pad2)") (class "Default")
      (node (ref "E3") (pin "2") (pinfunction "Q13_2") (pintype "output"))
    )
    (net (code "192") (name "unconnected-(E3A-Q14-Pad3)") (class "Default")
      (node (ref "E3") (pin "3") (pinfunction "Q14_3") (pintype "output"))
    )
    (net (code "193") (name "unconnected-(E4B-O-Pad5)") (class "Default")
      (node (ref "E4") (pin "5") (pinfunction "O_5") (pintype "open_collector"))
    )
    (net (code "194") (name "unconnected-(E5A-FE-Pad14)") (class "Default")
      (node (ref "E5") (pin "14") (pinfunction "FE_14") (pintype "tri_state"))
    )
    (net (code "195") (name "unconnected-(E5A-OE-Pad15)") (class "Default")
      (node (ref "E5") (pin "15") (pinfunction "OE_15") (pintype "tri_state"))
    )
    (net (code "196") (name "unconnected-(E5A-PE-Pad13)") (class "Default")
      (node (ref "E5") (pin "13") (pinfunction "PE_13") (pintype "tri_state"))
    )
    (net (code "197") (name "unconnected-(E5A-TBRE-Pad22)") (class "Default")
      (node (ref "E5") (pin "22") (pinfunction "TBRE_22") (pintype "tri_state"))
    )
    (net (code "198") (name "unconnected-(E6C-O-Pad10)") (class "Default")
      (node (ref "E6") (pin "10") (pinfunction "O_10") (pintype "output"))
    )
    (net (code "199") (name "unconnected-(E7D-O-Pad11)") (class "Default")
      (node (ref "E7") (pin "11") (pinfunction "O_11") (pintype "output"))
    )
    (net (code "200") (name "unconnected-(E11A-~{Q}-Pad6)") (class "Default")
      (node (ref "E11") (pin "6") (pinfunction "~{Q}_6") (pintype "output"))
    )
    (net (code "201") (name "unconnected-(E11B-Q-Pad9)") (class "Default")
      (node (ref "E11") (pin "9") (pinfunction "Q_9") (pintype "output"))
    )
    (net (code "202") (name "unconnected-(E12A-R2OUT-Pad9)") (class "Default")
      (node (ref "E12") (pin "9") (pinfunction "R2OUT_9") (pintype "output"))
    )
    (net (code "203") (name "unconnected-(LASTDEV-Pad8)") (class "Default")
      (node (ref "LASTDEV") (pin "8") (pinfunction "8_8") (pintype "passive"))
    )
    (net (code "204") (name "unconnected-(LASTDEV-Pad9)") (class "Default")
      (node (ref "LASTDEV") (pin "9") (pinfunction "9_9") (pintype "passive"))
    )
    (net (code "205") (name "unconnected-(LASTDEV-Pad10)") (class "Default")
      (node (ref "LASTDEV") (pin "10") (pinfunction "10_10") (pintype "passive"))
    )
    (net (code "206") (name "~{ACB00}") (class "Default")
      (node (ref "D34L") (pin "D") (pinfunction "4_D") (pintype "bidirectional"))
    )
    (net (code "207") (name "~{ACB01}") (class "Default")
      (node (ref "D34L") (pin "J") (pinfunction "8_J") (pintype "bidirectional"))
    )
    (net (code "208") (name "~{ACB02}") (class "Default")
      (node (ref "D34L") (pin "N") (pinfunction "12_N") (pintype "bidirectional"))
    )
    (net (code "209") (name "~{ACB03}") (class "Default")
      (node (ref "D34L") (pin "T") (pinfunction "16_T") (pintype "bidirectional"))
    )
    (net (code "210") (name "~{ACB04}") (class "Default")
      (node (ref "D34L") (pin "X") (pinfunction "20_X") (pintype "bidirectional"))
      (node (ref "E19") (pin "5") (pinfunction "O_5") (pintype "open_collector"))
    )
    (net (code "211") (name "~{ACB05}") (class "Default")
      (node (ref "D34L") (pin "BB") (pinfunction "24_BB") (pintype "bidirectional"))
      (node (ref "E18") (pin "3") (pinfunction "O_3") (pintype "open_collector"))
    )
    (net (code "212") (name "~{ACB06}") (class "Default")
      (node (ref "D34L") (pin "FF") (pinfunction "28_FF") (pintype "bidirectional"))
      (node (ref "E17") (pin "3") (pinfunction "O_3") (pintype "open_collector"))
    )
    (net (code "213") (name "~{ACB07}") (class "Default")
      (node (ref "D34L") (pin "LL") (pinfunction "32_LL") (pintype "bidirectional"))
      (node (ref "E17") (pin "5") (pinfunction "O_5") (pintype "open_collector"))
    )
    (net (code "214") (name "~{ACB08}") (class "Default")
      (node (ref "D34L") (pin "RR") (pinfunction "36_RR") (pintype "bidirectional"))
      (node (ref "E4") (pin "3") (pinfunction "O_3") (pintype "open_collector"))
    )
    (net (code "215") (name "~{ACB09}") (class "Default")
      (node (ref "D34L") (pin "F") (pinfunction "6_F") (pintype "bidirectional"))
      (node (ref "E21") (pin "3") (pinfunction "O_3") (pintype "open_collector"))
    )
    (net (code "216") (name "~{ACB10}") (class "Default")
      (node (ref "D34L") (pin "L") (pinfunction "10_L") (pintype "bidirectional"))
      (node (ref "E21") (pin "5") (pinfunction "O_5") (pintype "open_collector"))
    )
    (net (code "217") (name "~{ACB11}") (class "Default")
      (node (ref "D34L") (pin "R") (pinfunction "14_R") (pintype "bidirectional"))
      (node (ref "E20") (pin "3") (pinfunction "O_3") (pintype "open_collector"))
    )
    (net (code "218") (name "~{ACCLEAR}") (class "Default")
      (node (ref "D34L") (pin "DD") (pinfunction "26_DD") (pintype "bidirectional"))
      (node (ref "E18") (pin "5") (pinfunction "O_5") (pintype "open_collector"))
    )
    (net (code "219") (name "~{BINIT}") (class "Default")
      (node (ref "D36L") (pin "TT") (pinfunction "38_TT") (pintype "bidirectional"))
      (node (ref "E10") (pin "3") (pinfunction "I_3") (pintype "input"))
      (node (ref "E8") (pin "13") (pinfunction "I1_13") (pintype "input"))
      (node (ref "LASTDEV") (pin "2") (pinfunction "2_2") (pintype "passive"))
    )
    (net (code "220") (name "~{BMB03}") (class "Default")
      (node (ref "D35L") (pin "T") (pinfunction "16_T") (pintype "bidirectional"))
    )
    (net (code "221") (name "~{BMB04}") (class "Default")
      (node (ref "D35L") (pin "BB") (pinfunction "24_BB") (pintype "bidirectional"))
    )
    (net (code "222") (name "~{BMB05}") (class "Default")
      (node (ref "D35L") (pin "LL") (pinfunction "32_LL") (pintype "bidirectional"))
    )
    (net (code "223") (name "~{BMB06}") (class "Default")
      (node (ref "D35L") (pin "F") (pinfunction "6_F") (pintype "bidirectional"))
    )
    (net (code "224") (name "~{BMB07}") (class "Default")
      (node (ref "D35L") (pin "R") (pinfunction "14_R") (pintype "bidirectional"))
    )
    (net (code "225") (name "~{BMB08}") (class "Default")
      (node (ref "D35L") (pin "Z") (pinfunction "22_Z") (pintype "bidirectional"))
    )
    (net (code "226") (name "~{BRUN}") (class "Default")
      (node (ref "D34L") (pin "JJ") (pinfunction "30_JJ") (pintype "bidirectional"))
    )
    (net (code "227") (name "~{B}") (class "Default")
      (node (ref "B") (pin "10") (pinfunction "10_10") (pintype "passive"))
      (node (ref "B") (pin "12") (pinfunction "12_12") (pintype "passive"))
      (node (ref "B") (pin "14") (pinfunction "14_14") (pintype "passive"))
      (node (ref "B") (pin "16") (pinfunction "16_16") (pintype "passive"))
      (node (ref "B") (pin "2") (pinfunction "2_2") (pintype "passive"))
      (node (ref "B") (pin "4") (pinfunction "4_4") (pintype "passive"))
      (node (ref "B") (pin "6") (pinfunction "6_6") (pintype "passive"))
      (node (ref "B") (pin "8") (pinfunction "8_8") (pintype "passive"))
      (node (ref "E6") (pin "3") (pinfunction "I1_3") (pintype "input"))
    )
    (net (code "228") (name "~{INT_RQ}") (class "Default")
      (node (ref "D34L") (pin "Z") (pinfunction "22_Z") (pintype "bidirectional"))
      (node (ref "E23") (pin "3") (pinfunction "O_3") (pintype "open_collector"))
      (node (ref "E23") (pin "5") (pinfunction "O_5") (pintype "open_collector"))
    )
    (net (code "229") (name "~{IOS}") (class "Default")
      (node (ref "D34L") (pin "V") (pinfunction "18_V") (pintype "bidirectional"))
      (node (ref "E19") (pin "3") (pinfunction "O_3") (pintype "open_collector"))
      (node (ref "E20") (pin "5") (pinfunction "O_5") (pintype "open_collector"))
    )
    (net (code "230") (name "~{KCC}") (class "Default")
      (node (ref "E10") (pin "1") (pinfunction "I_1") (pintype "input"))
      (node (ref "E5") (pin "18") (pinfunction "~{DRR}_18") (pintype "input"))
      (node (ref "E7") (pin "3") (pinfunction "O_3") (pintype "output"))
      (node (ref "E8") (pin "12") (pinfunction "I0_12") (pintype "input"))
    )
    (net (code "231") (name "~{K}") (class "Default")
      (node (ref "E6") (pin "2") (pinfunction "I0_2") (pintype "input"))
      (node (ref "K") (pin "10") (pinfunction "10_10") (pintype "passive"))
      (node (ref "K") (pin "12") (pinfunction "12_12") (pintype "passive"))
      (node (ref "K") (pin "14") (pinfunction "14_14") (pintype "passive"))
      (node (ref "K") (pin "16") (pinfunction "16_16") (pintype "passive"))
      (node (ref "K") (pin "2") (pinfunction "2_2") (pintype "passive"))
      (node (ref "K") (pin "4") (pinfunction "4_4") (pintype "passive"))
      (node (ref "K") (pin "6") (pinfunction "6_6") (pintype "passive"))
      (node (ref "K") (pin "8") (pinfunction "8_8") (pintype "passive"))
    )
    (net (code "232") (name "~{P}") (class "Default")
      (node (ref "E6") (pin "5") (pinfunction "I0_5") (pintype "input"))
      (node (ref "P") (pin "10") (pinfunction "10_10") (pintype "passive"))
      (node (ref "P") (pin "12") (pinfunction "12_12") (pintype "passive"))
      (node (ref "P") (pin "14") (pinfunction "14_14") (pintype "passive"))
      (node (ref "P") (pin "16") (pinfunction "16_16") (pintype "passive"))
      (node (ref "P") (pin "2") (pinfunction "2_2") (pintype "passive"))
      (node (ref "P") (pin "4") (pinfunction "4_4") (pintype "passive"))
      (node (ref "P") (pin "6") (pinfunction "6_6") (pintype "passive"))
      (node (ref "P") (pin "8") (pinfunction "8_8") (pintype "passive"))
    )
    (net (code "233") (name "~{RXL}") (class "Default")
      (node (ref "E6") (pin "11") (pinfunction "I0_11") (pintype "input"))
      (node (ref "R14") (pin "2") (pinfunction "2_2") (pintype "passive"))
    )
    (net (code "234") (name "~{TCF}") (class "Default")
      (node (ref "E11") (pin "1") (pinfunction "CLR_1") (pintype "input"))
      (node (ref "E7") (pin "6") (pinfunction "O_6") (pintype "output"))
    )
    (net (code "235") (name "~{TPC}") (class "Default")
      (node (ref "E5") (pin "23") (pinfunction "~{TBRL}_23") (pintype "input"))
      (node (ref "E7") (pin "8") (pinfunction "O_8") (pintype "output"))
    )
    (net (code "236") (name "~{T}") (class "Default")
      (node (ref "E6") (pin "6") (pinfunction "I1_6") (pintype "input"))
      (node (ref "T") (pin "10") (pinfunction "10_10") (pintype "passive"))
      (node (ref "T") (pin "12") (pinfunction "12_12") (pintype "passive"))
      (node (ref "T") (pin "14") (pinfunction "14_14") (pintype "passive"))
      (node (ref "T") (pin "16") (pinfunction "16_16") (pintype "passive"))
      (node (ref "T") (pin "2") (pinfunction "2_2") (pintype "passive"))
      (node (ref "T") (pin "4") (pinfunction "4_4") (pintype "passive"))
      (node (ref "T") (pin "6") (pinfunction "6_6") (pintype "passive"))
      (node (ref "T") (pin "8") (pinfunction "8_8") (pintype "passive"))
    )
  )
)
